# ARK.net
KiCad netlist of a schematic drawn in EAGLE
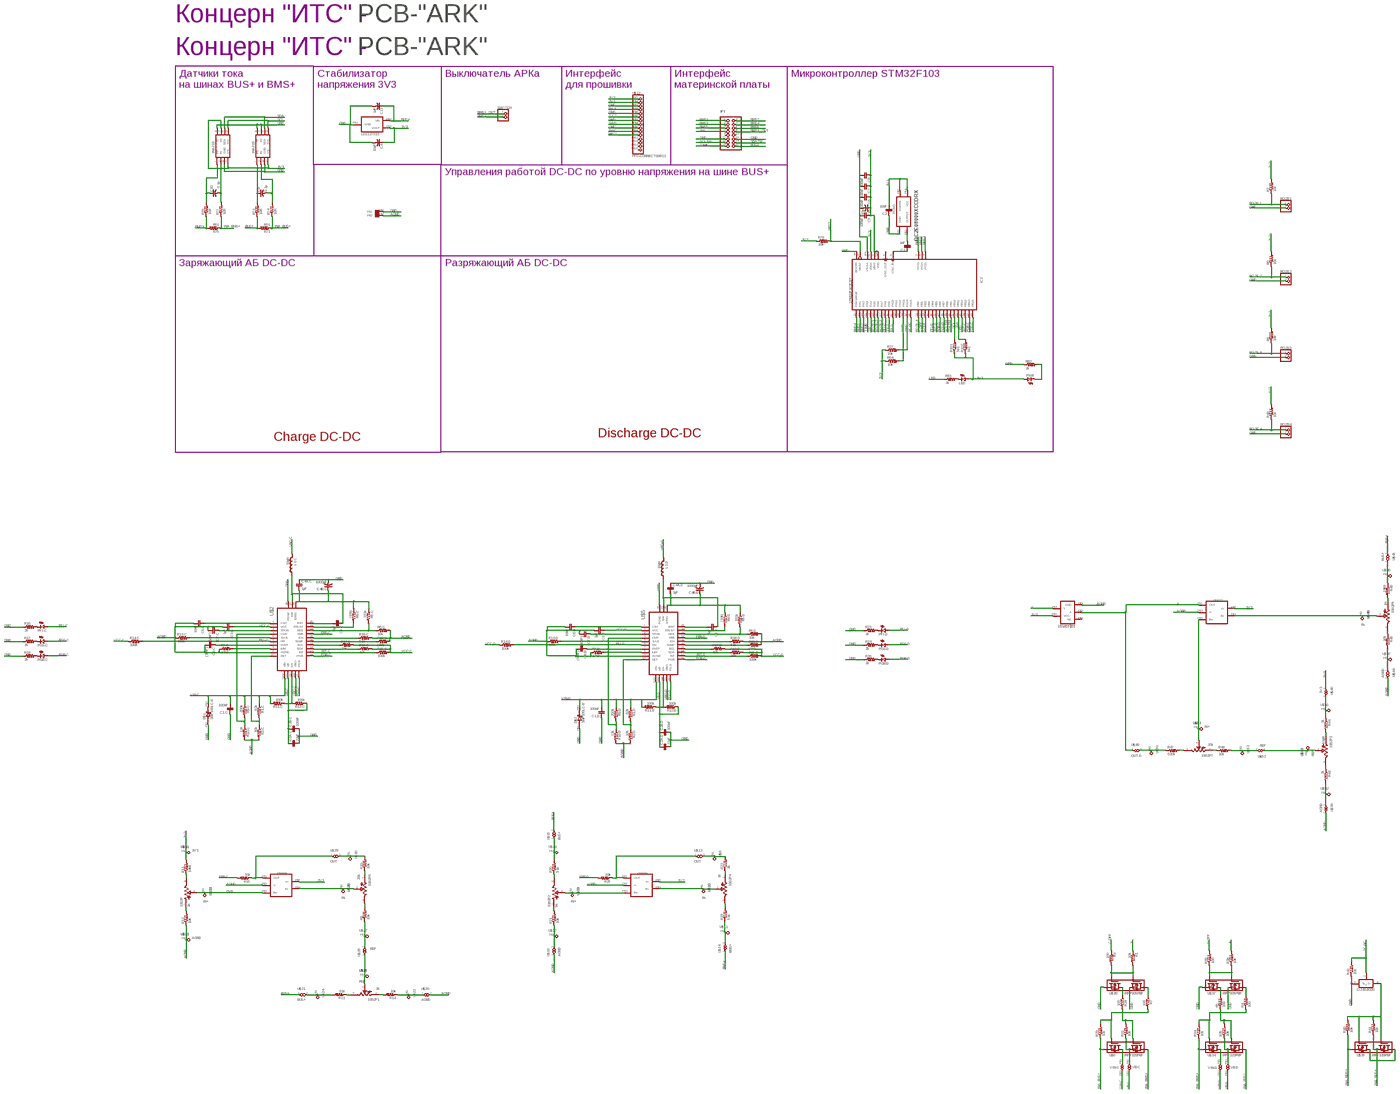
[diagram p0: schematic, sheet 1, overview]
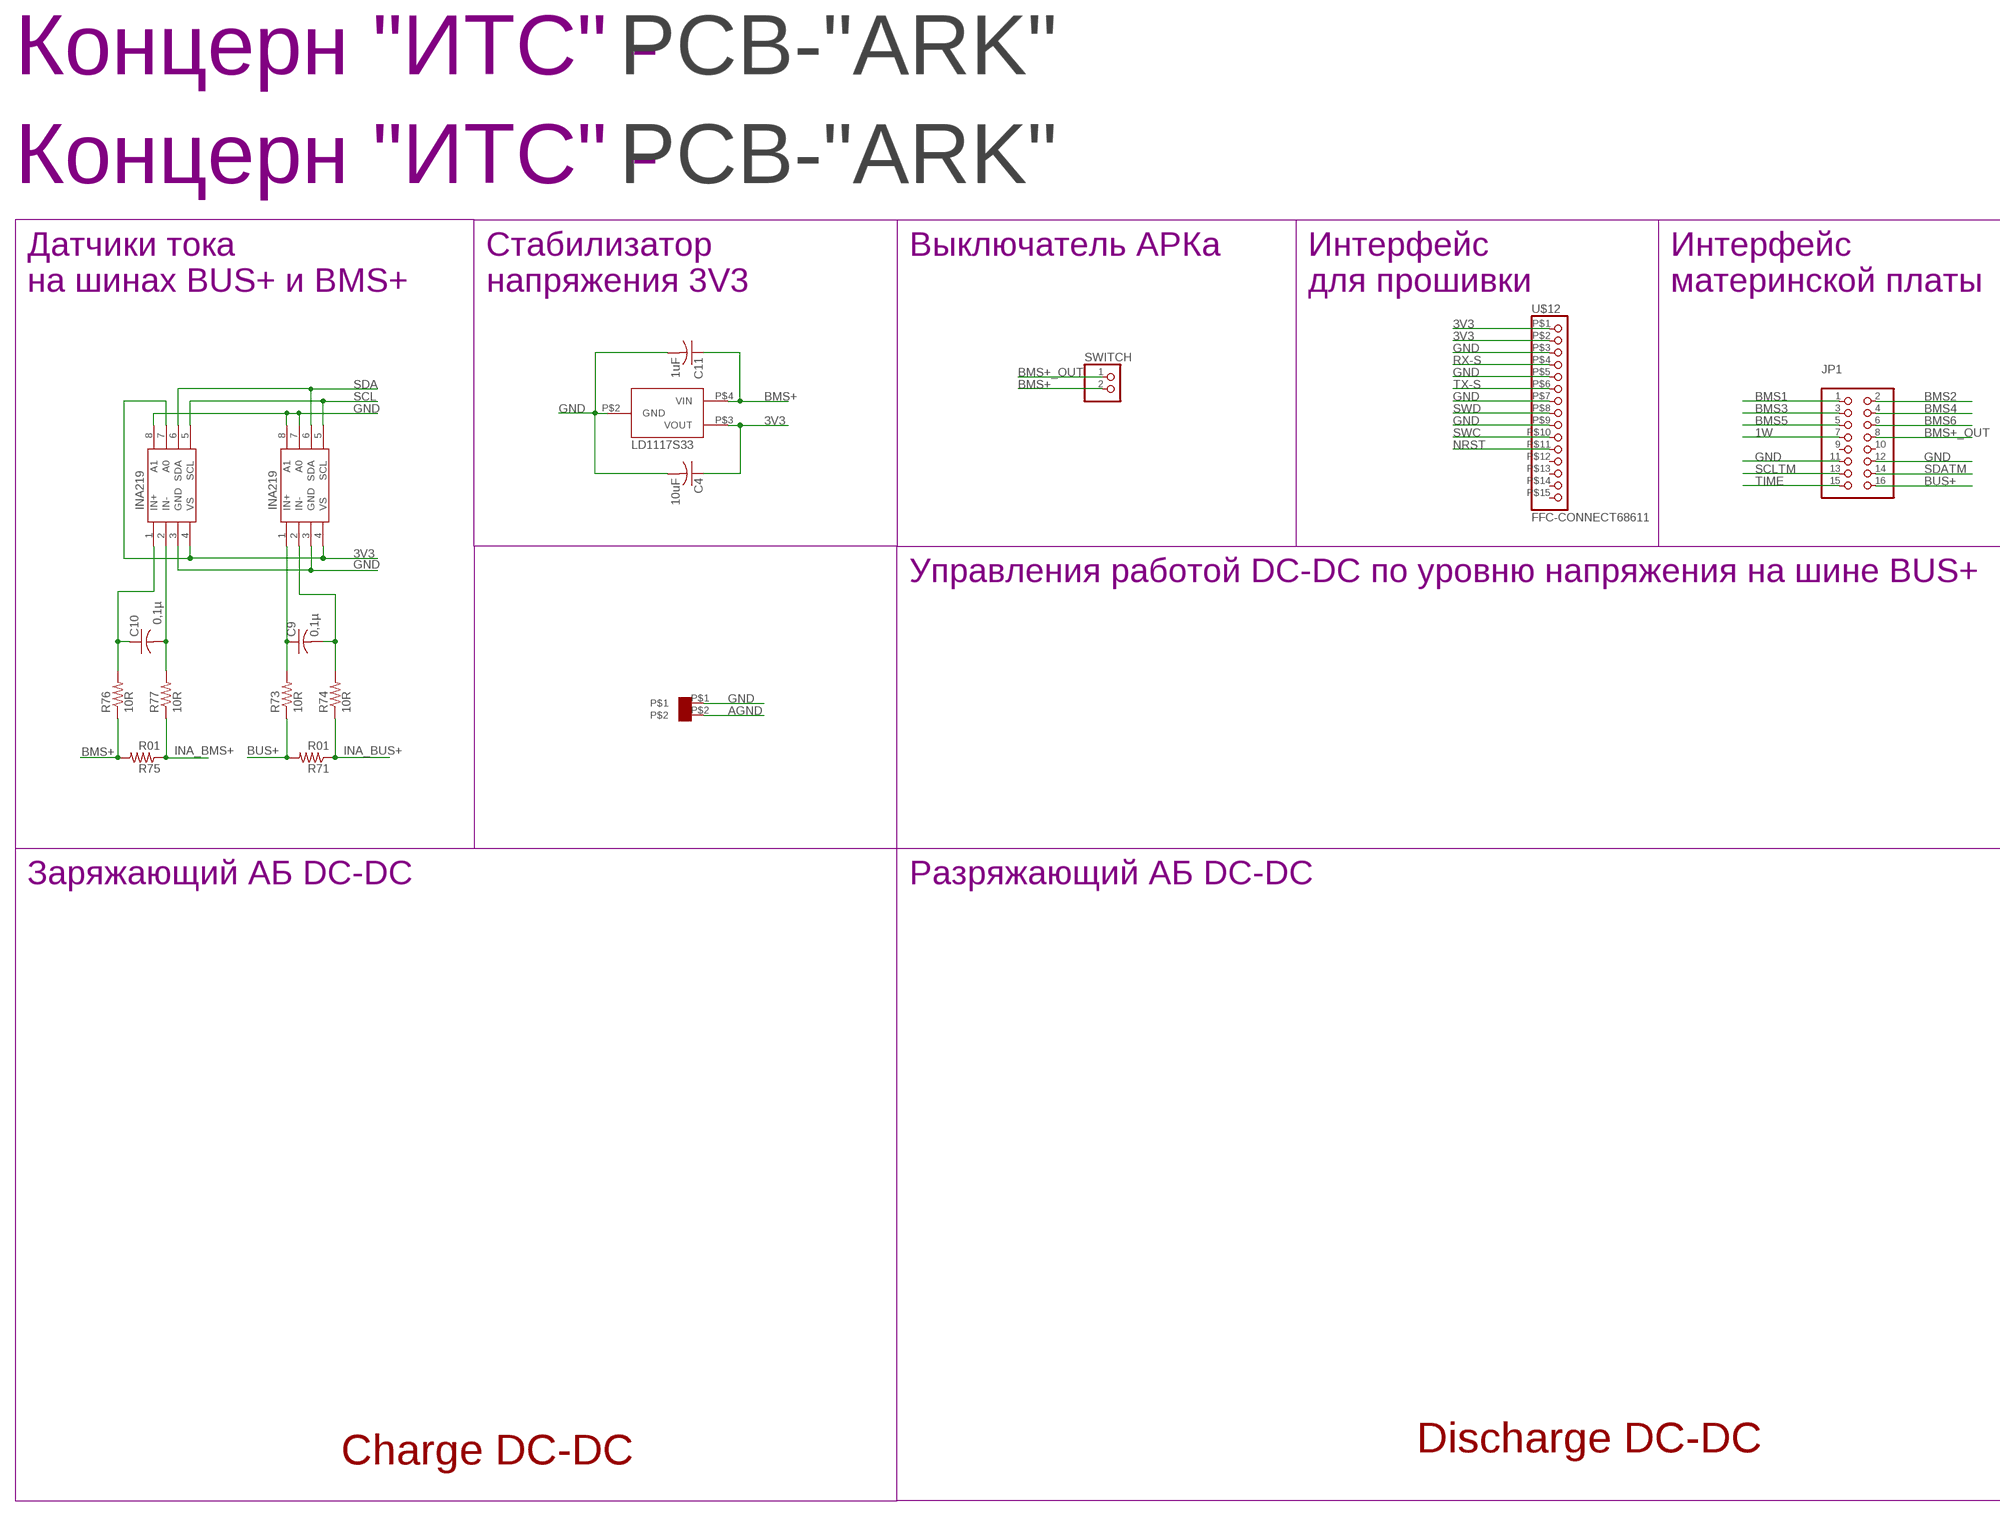
[diagram p1: schematic, sheet 1, part 1 of 4]
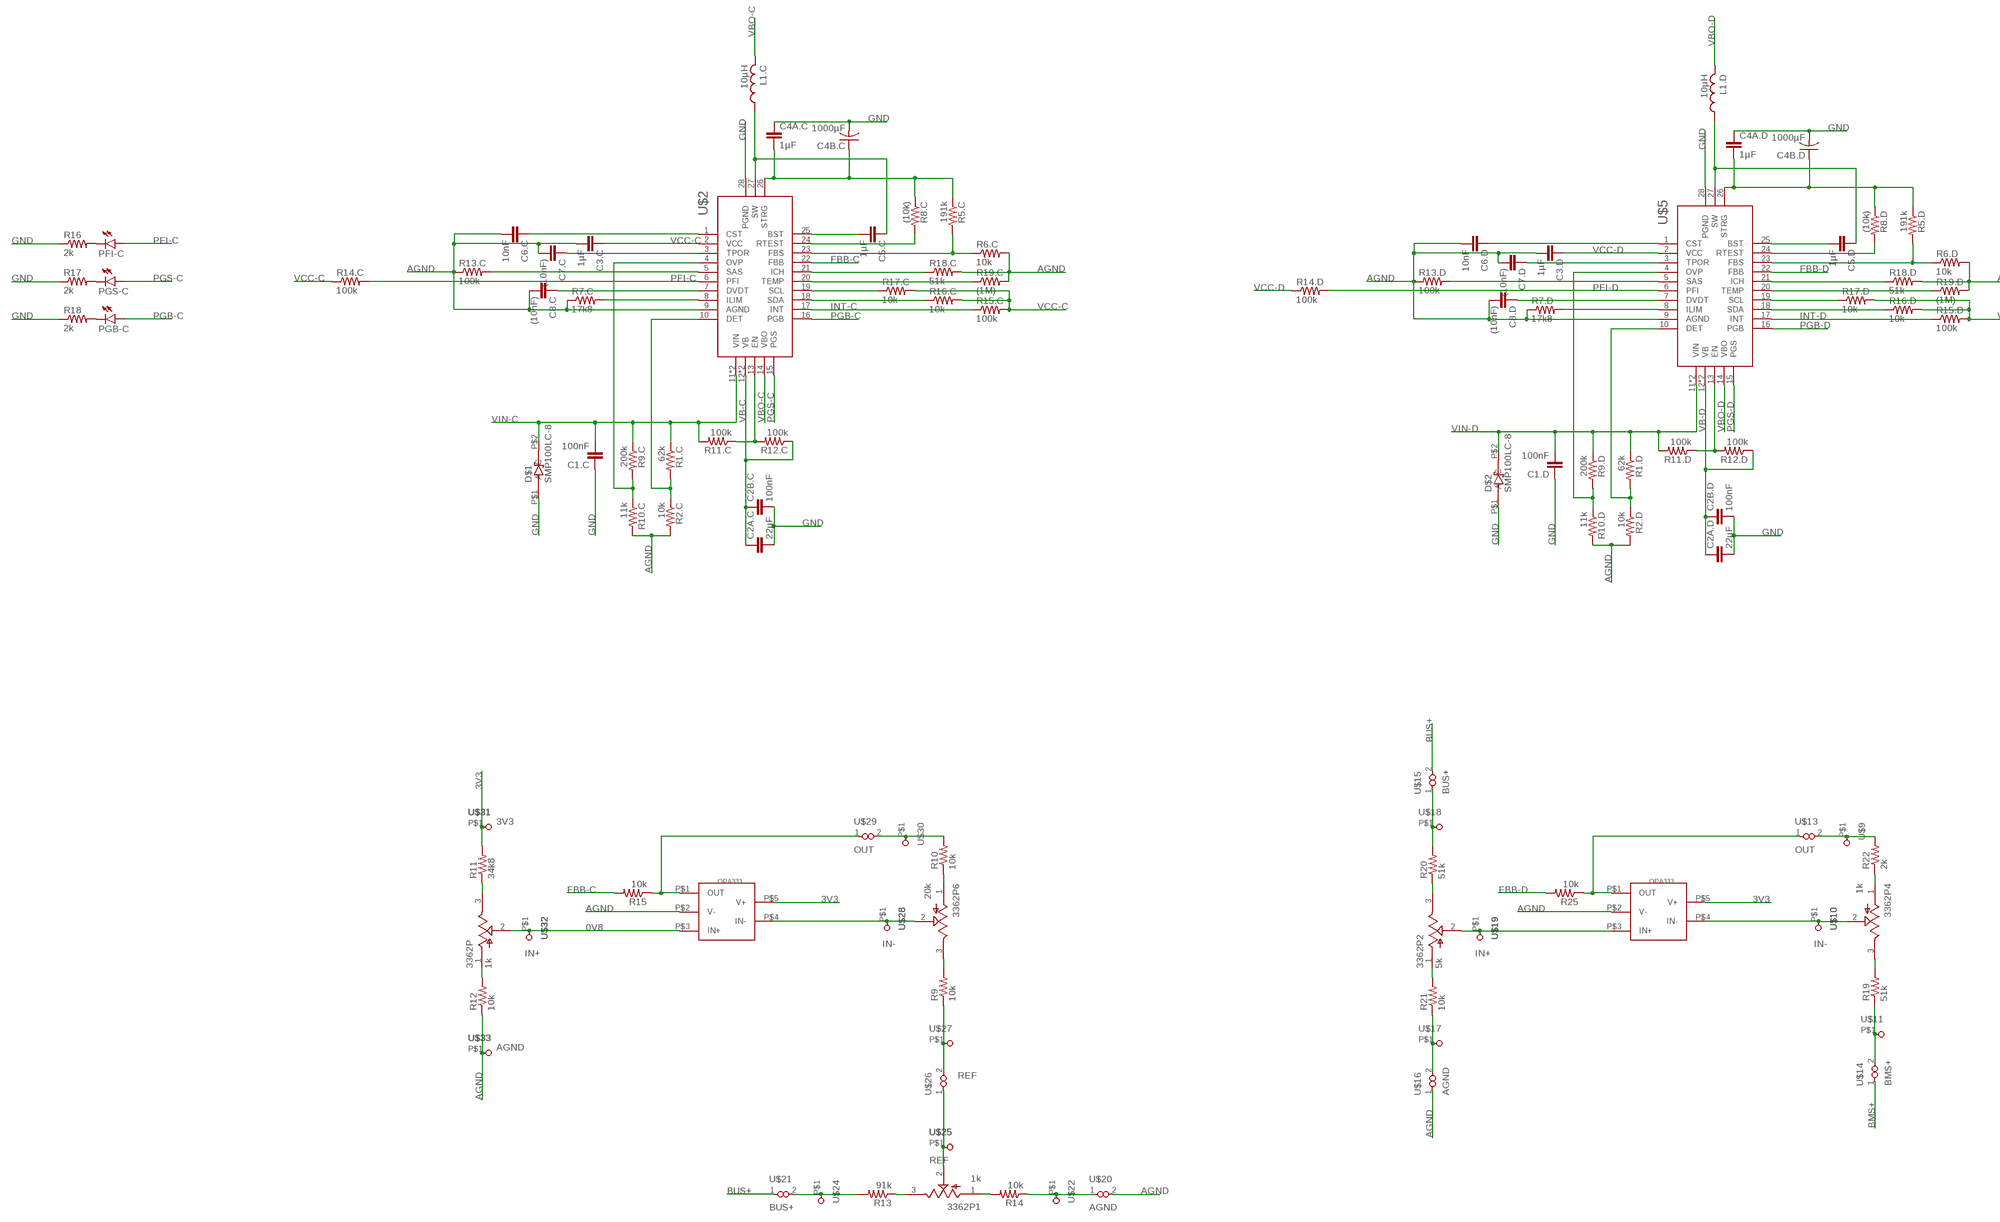
[diagram p2: schematic, sheet 1, part 2 of 4]
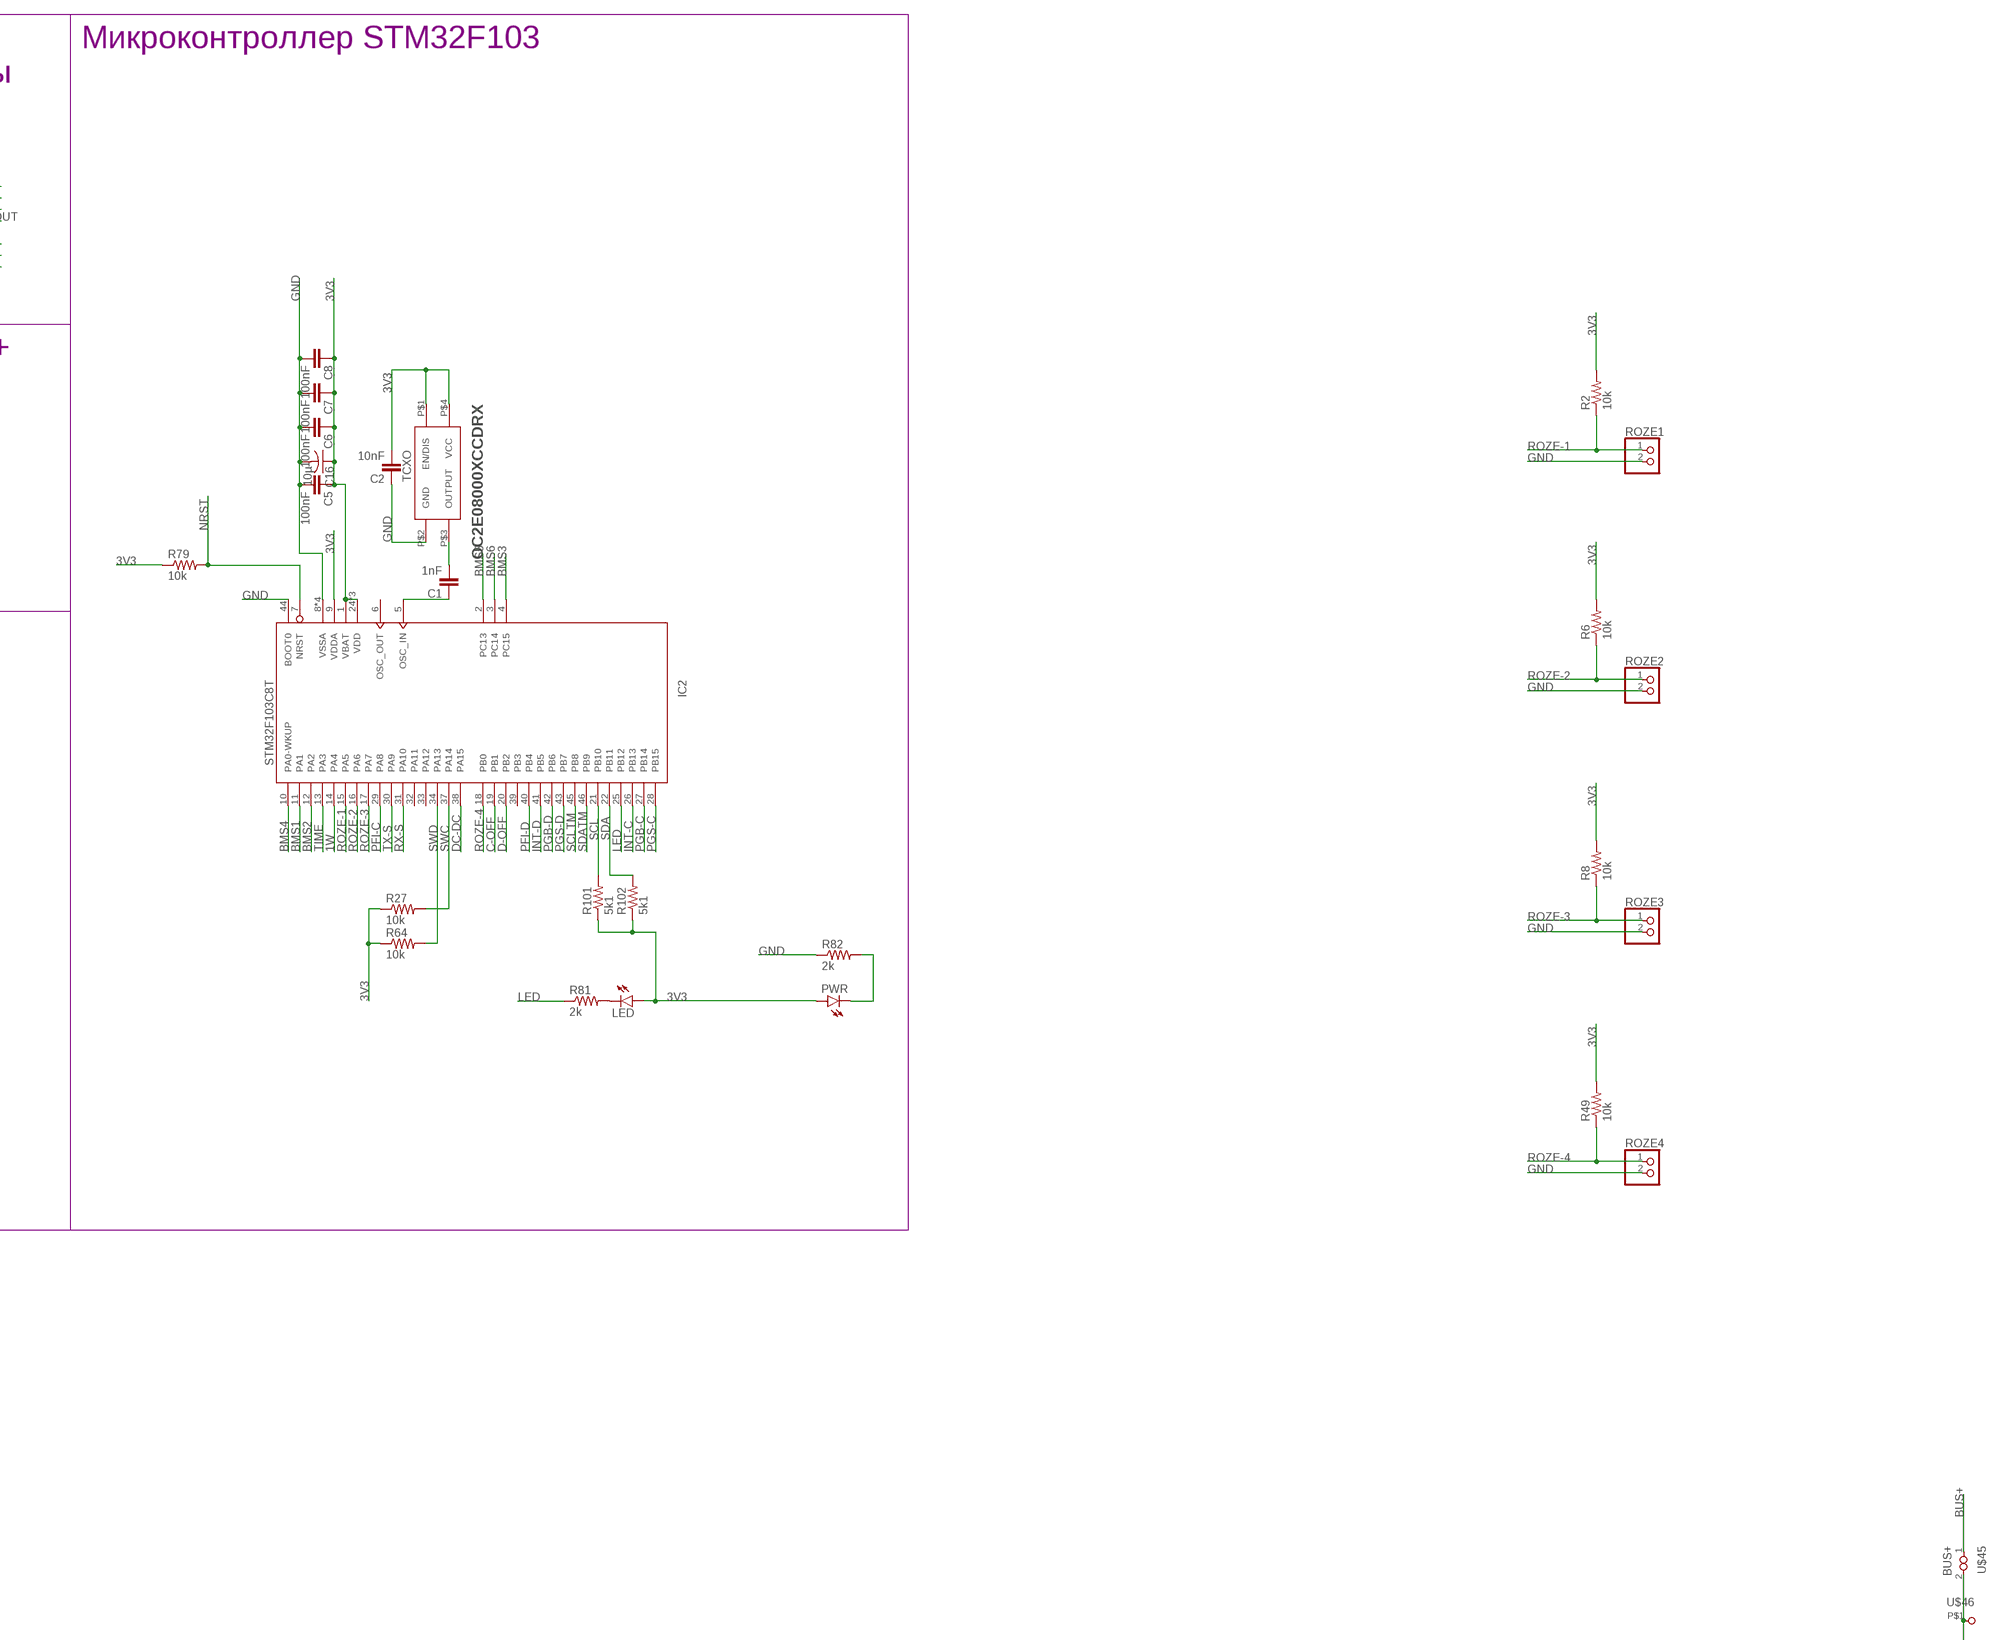
[diagram p3: schematic, sheet 1, part 3 of 4]
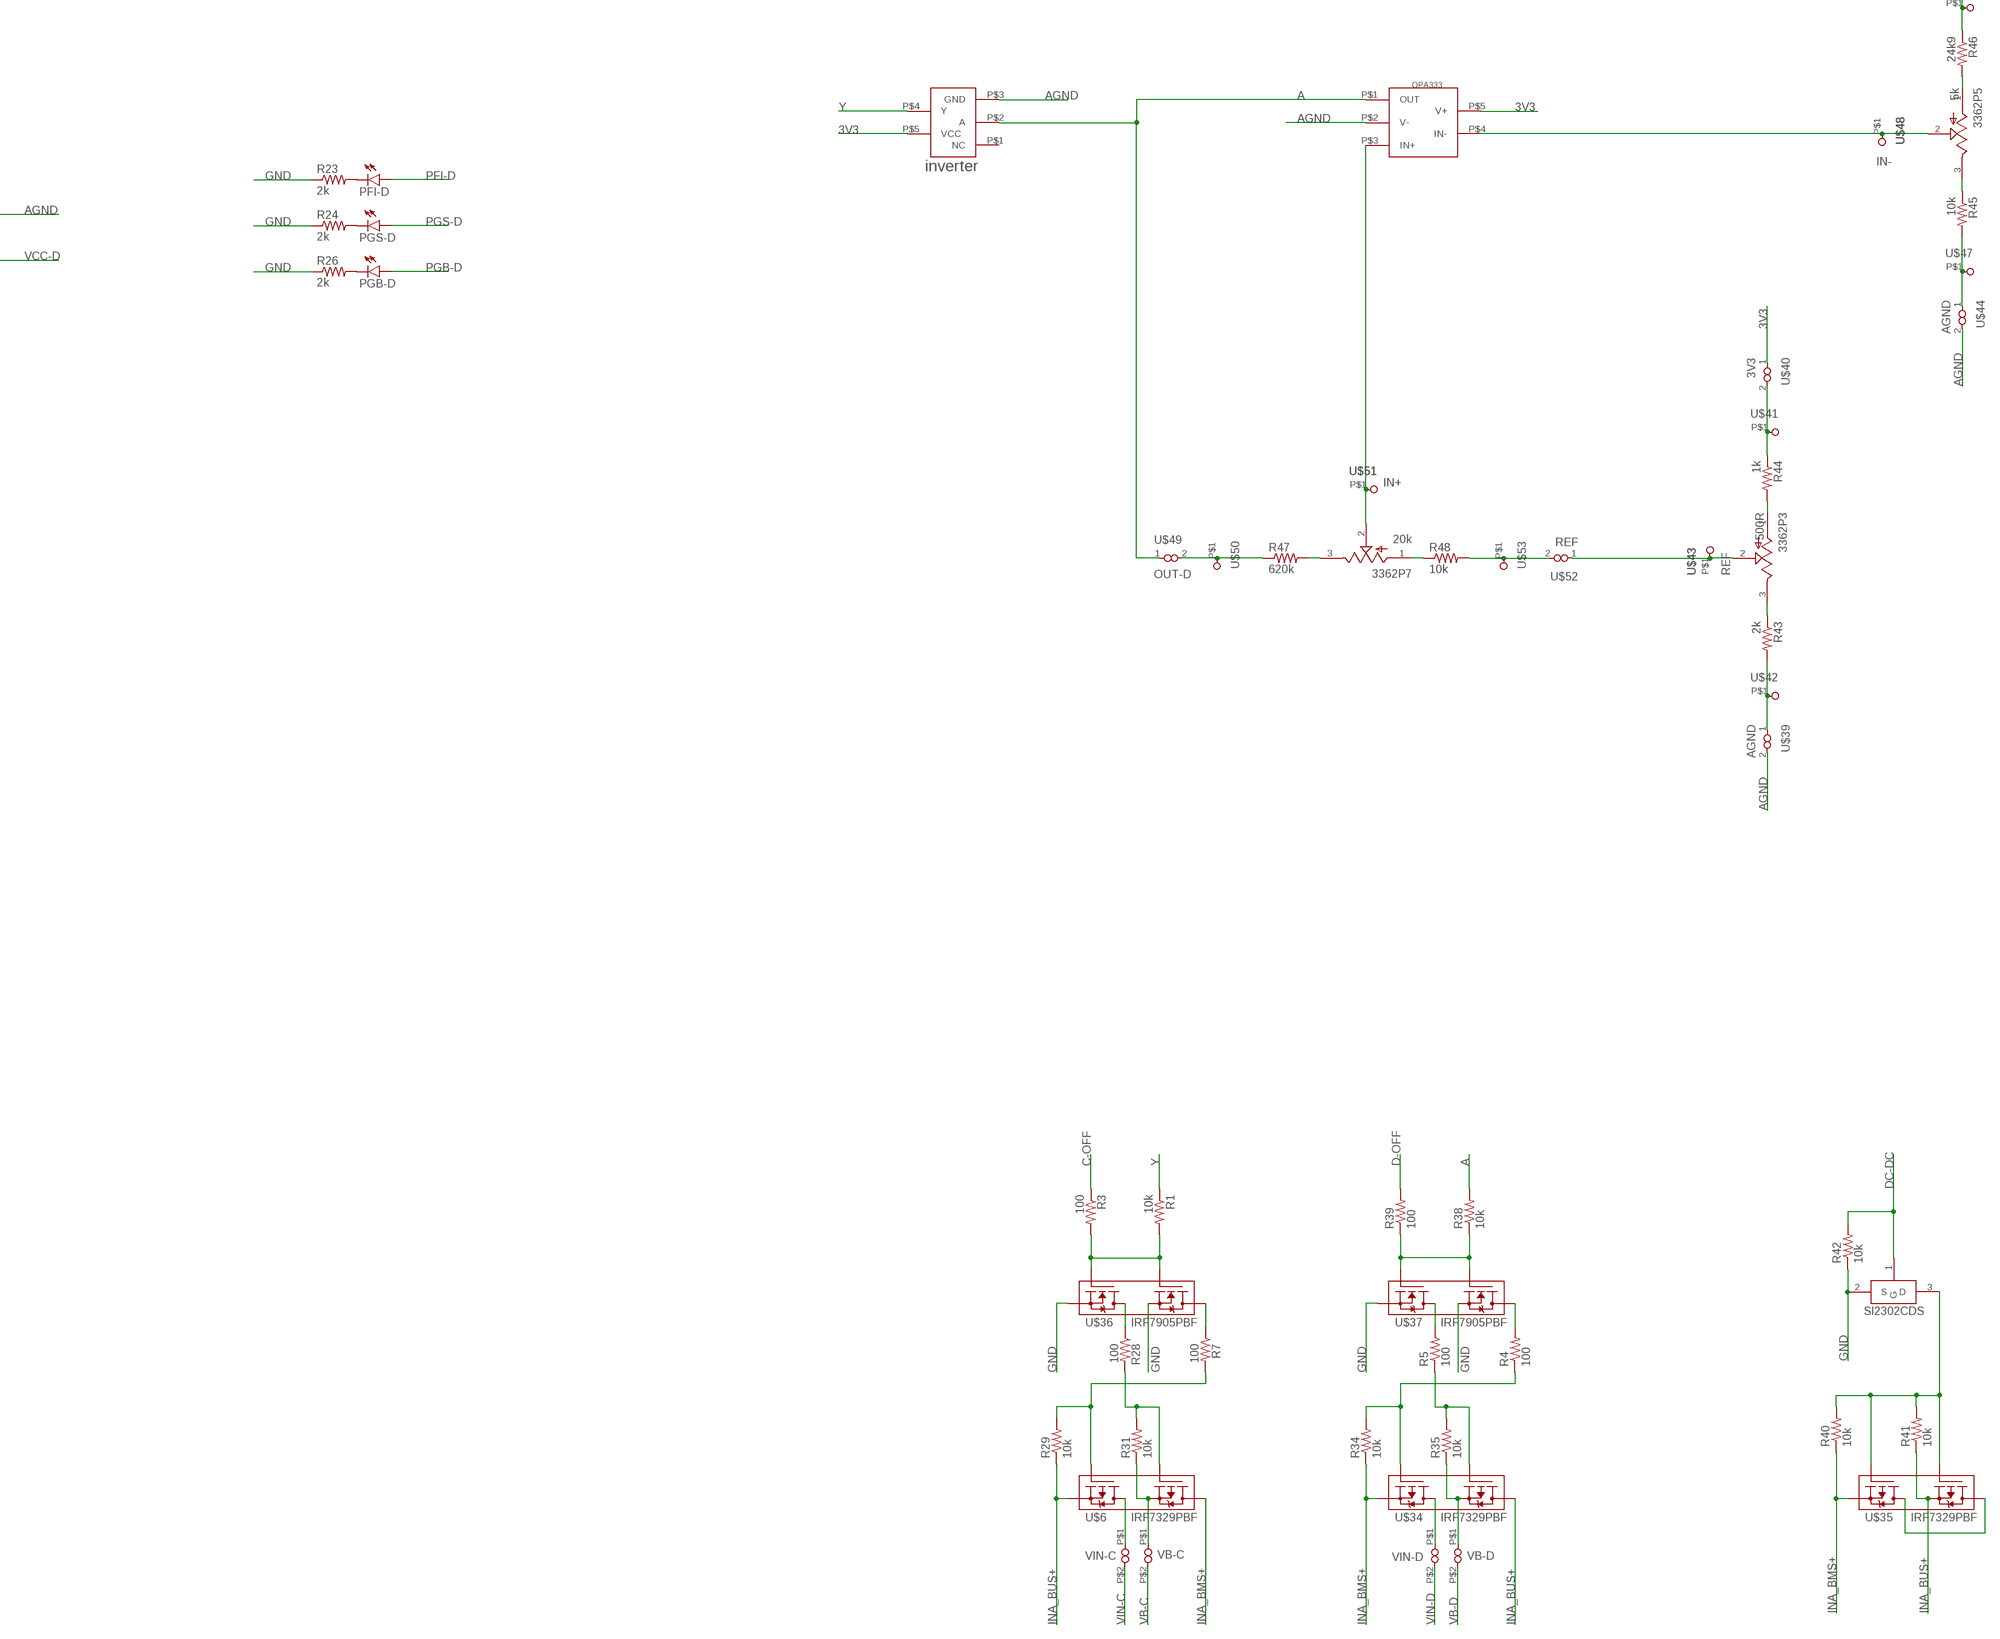
[diagram p4: schematic, sheet 1, part 4 of 4]

(export (version "E")
  (design (tool "Eeschema 10.0.6"))
  (components
    (comp (ref "3362P")
      (value "1k")
      (footprint "eagle-import:TRIM_3362P-1-502LF")
      (fields (field (name "MF") "Bourns") (field (name "MP") "3362P-1-502LF"))
      (libsource (lib "eagle-import") (part "3362P-1-502LF"))
    )
    (comp (ref "3362P1")
      (value "1k")
      (footprint "eagle-import:TRIM_3362P-1-502LF")
      (fields (field (name "MF") "Bourns") (field (name "MP") "3362P-1-502LF"))
      (libsource (lib "eagle-import") (part "3362P-1-502LF"))
    )
    (comp (ref "3362P2")
      (value "5k")
      (footprint "eagle-import:TRIM_3362P-1-502LF")
      (fields (field (name "MF") "Bourns") (field (name "MP") "3362P-1-502LF"))
      (libsource (lib "eagle-import") (part "3362P-1-502LF"))
    )
    (comp (ref "3362P3")
      (value "500R")
      (footprint "eagle-import:TRIM_3362P-1-502LF")
      (fields (field (name "MF") "Bourns") (field (name "MP") "3362P-1-502LF"))
      (libsource (lib "eagle-import") (part "3362P-1-502LF"))
    )
    (comp (ref "3362P4")
      (value "1k")
      (footprint "eagle-import:TRIM_3362P-1-502LF")
      (fields (field (name "MF") "Bourns") (field (name "MP") "3362P-1-502LF"))
      (libsource (lib "eagle-import") (part "3362P-1-502LF"))
    )
    (comp (ref "3362P5")
      (value "5k")
      (footprint "eagle-import:TRIM_3362P-1-502LF")
      (fields (field (name "MF") "Bourns") (field (name "MP") "3362P-1-502LF"))
      (libsource (lib "eagle-import") (part "3362P-1-502LF"))
    )
    (comp (ref "3362P6")
      (value "20k")
      (footprint "eagle-import:TRIM_3362P-1-502LF")
      (fields (field (name "MF") "Bourns") (field (name "MP") "3362P-1-502LF"))
      (libsource (lib "eagle-import") (part "3362P-1-502LF"))
    )
    (comp (ref "3362P7")
      (value "20k")
      (footprint "eagle-import:TRIM_3362P-1-502LF")
      (fields (field (name "MF") "Bourns") (field (name "MP") "3362P-1-502LF"))
      (libsource (lib "eagle-import") (part "3362P-1-502LF"))
    )
    (comp (ref "C1")
      (value "1nF")
      (footprint "eagle-import:C0603")
      (libsource (lib "eagle-import") (part "C-EUC0603"))
    )
    (comp (ref "C1.C")
      (value "100nF")
      (footprint "eagle-import:C0603")
      (libsource (lib "eagle-import") (part "C-EUC0603"))
    )
    (comp (ref "C1.D")
      (value "100nF")
      (footprint "eagle-import:C0603")
      (libsource (lib "eagle-import") (part "C-EUC0603"))
    )
    (comp (ref "C2")
      (value "10nF")
      (footprint "eagle-import:C0603")
      (libsource (lib "eagle-import") (part "C-EUC0603"))
    )
    (comp (ref "C2A.C")
      (value "22µF")
      (footprint "eagle-import:C1206")
      (libsource (lib "eagle-import") (part "C-EUC1206"))
    )
    (comp (ref "C2A.D")
      (value "22µF")
      (footprint "eagle-import:C1206")
      (libsource (lib "eagle-import") (part "C-EUC1206"))
    )
    (comp (ref "C2B.C")
      (value "100nF")
      (footprint "eagle-import:C0603")
      (libsource (lib "eagle-import") (part "C-EUC0603"))
    )
    (comp (ref "C2B.D")
      (value "100nF")
      (footprint "eagle-import:C0603")
      (libsource (lib "eagle-import") (part "C-EUC0603"))
    )
    (comp (ref "C3.C")
      (value "1µF")
      (footprint "eagle-import:C0603")
      (libsource (lib "eagle-import") (part "C-EUC0603"))
    )
    (comp (ref "C3.D")
      (value "1µF")
      (footprint "eagle-import:C0603")
      (libsource (lib "eagle-import") (part "C-EUC0603"))
    )
    (comp (ref "C4")
      (value "10uF")
      (footprint "eagle-import:ECAP-SMD-D4")
      (libsource (lib "eagle-import") (part "ECAP1UF"))
    )
    (comp (ref "C4A.C")
      (value "1µF")
      (footprint "eagle-import:C1206")
      (libsource (lib "eagle-import") (part "C-EUC1206"))
    )
    (comp (ref "C4A.D")
      (value "1µF")
      (footprint "eagle-import:C1206")
      (libsource (lib "eagle-import") (part "C-EUC1206"))
    )
    (comp (ref "C4B.C")
      (value "1000µF")
      (footprint "eagle-import:ECAP1000-CMD")
      (libsource (lib "eagle-import") (part "ECAPECAP1000"))
    )
    (comp (ref "C4B.D")
      (value "1000µF")
      (footprint "eagle-import:ECAP1000-CMD")
      (libsource (lib "eagle-import") (part "ECAPECAP1000"))
    )
    (comp (ref "C5")
      (value "100nF")
      (footprint "eagle-import:C0603")
      (libsource (lib "eagle-import") (part "C-EUC0603"))
    )
    (comp (ref "C5.C")
      (value "1µF")
      (footprint "eagle-import:C0603")
      (libsource (lib "eagle-import") (part "C-EUC0603"))
    )
    (comp (ref "C5.D")
      (value "1µF")
      (footprint "eagle-import:C0603")
      (libsource (lib "eagle-import") (part "C-EUC0603"))
    )
    (comp (ref "C6")
      (value "100nF")
      (footprint "eagle-import:C0603")
      (libsource (lib "eagle-import") (part "C-EUC0603"))
    )
    (comp (ref "C6.C")
      (value "10nF")
      (footprint "eagle-import:C0603")
      (libsource (lib "eagle-import") (part "C-EUC0603"))
    )
    (comp (ref "C6.D")
      (value "10nF")
      (footprint "eagle-import:C0603")
      (libsource (lib "eagle-import") (part "C-EUC0603"))
    )
    (comp (ref "C7")
      (value "100nF")
      (footprint "eagle-import:C0603")
      (libsource (lib "eagle-import") (part "C-EUC0603"))
    )
    (comp (ref "C7.C")
      (value "(10nF)")
      (footprint "eagle-import:C0603")
      (libsource (lib "eagle-import") (part "C-EUC0603"))
    )
    (comp (ref "C7.D")
      (value "(10nF)")
      (footprint "eagle-import:C0603")
      (libsource (lib "eagle-import") (part "C-EUC0603"))
    )
    (comp (ref "C8")
      (value "100nF")
      (footprint "eagle-import:C0603")
      (libsource (lib "eagle-import") (part "C-EUC0603"))
    )
    (comp (ref "C8.C")
      (value "(10nF)")
      (footprint "eagle-import:C0603")
      (libsource (lib "eagle-import") (part "C-EUC0603"))
    )
    (comp (ref "C8.D")
      (value "(10nF)")
      (footprint "eagle-import:C0603")
      (libsource (lib "eagle-import") (part "C-EUC0603"))
    )
    (comp (ref "C9")
      (value "0,1µ")
      (footprint "eagle-import:C0603")
      (libsource (lib "eagle-import") (part "C-USC0603"))
    )
    (comp (ref "C10")
      (value "0,1µ")
      (footprint "eagle-import:C0603")
      (libsource (lib "eagle-import") (part "C-USC0603"))
    )
    (comp (ref "C11")
      (value "1uF")
      (footprint "eagle-import:ECAP-SMD-D4")
      (libsource (lib "eagle-import") (part "ECAP1UF"))
    )
    (comp (ref "C16")
      (value "10µ")
      (footprint "eagle-import:C1206")
      (libsource (lib "eagle-import") (part "C-USC1206"))
    )
    (comp (ref "D$1")
      (value "SMP100LC-8")
      (footprint "eagle-import:SMB")
      (libsource (lib "eagle-import") (part "SMP100LC-8"))
    )
    (comp (ref "D$2")
      (value "SMP100LC-8")
      (footprint "eagle-import:SMB")
      (libsource (lib "eagle-import") (part "SMP100LC-8"))
    )
    (comp (ref "IC2")
      (value "STM32F103C8T")
      (footprint "eagle-import:LQFP48")
      (libsource (lib "eagle-import") (part "STM32F103CT8"))
    )
    (comp (ref "INA219#1")
      (value "INA219AID")
      (footprint "eagle-import:SOT23-8")
      (libsource (lib "eagle-import") (part "INA219AID"))
    )
    (comp (ref "INA219#2")
      (value "INA219AID")
      (footprint "eagle-import:SOT23-8")
      (libsource (lib "eagle-import") (part "INA219AID"))
    )
    (comp (ref "INVERT1")
      (value "INVERTER.")
      (footprint "eagle-import:SC70")
      (libsource (lib "eagle-import") (part "INVERTER."))
    )
    (comp (ref "JP1")
      (value "PINHD-2X8")
      (footprint "eagle-import:2X08")
      (libsource (lib "eagle-import") (part "PINHD-2X8"))
    )
    (comp (ref "L1.C")
      (value "10µH")
      (footprint "eagle-import:L_12X12")
      (libsource (lib "eagle-import") (part "L_10MKH"))
    )
    (comp (ref "L1.D")
      (value "10µH")
      (footprint "eagle-import:L_12X12")
      (libsource (lib "eagle-import") (part "L_10MKH"))
    )
    (comp (ref "LD1117S33")
      (value "LD1117S33")
      (footprint "eagle-import:SOT223")
      (libsource (lib "eagle-import") (part "LD1117S33"))
    )
    (comp (ref "LED")
      (value "LEDCHIPLED_0603")
      (footprint "eagle-import:CHIPLED_0603")
      (libsource (lib "eagle-import") (part "LEDCHIPLED_0603"))
    )
    (comp (ref "OPA1")
      (value "OPA333")
      (footprint "eagle-import:SOT23-5")
      (libsource (lib "eagle-import") (part "OPA333"))
    )
    (comp (ref "OPA2")
      (value "OPA333")
      (footprint "eagle-import:SOT23-5")
      (libsource (lib "eagle-import") (part "OPA333"))
    )
    (comp (ref "OPA3")
      (value "OPA333")
      (footprint "eagle-import:SOT23-5")
      (libsource (lib "eagle-import") (part "OPA333"))
    )
    (comp (ref "PFI-C")
      (value "LEDCHIPLED_0603")
      (footprint "eagle-import:CHIPLED_0603")
      (libsource (lib "eagle-import") (part "LEDCHIPLED_0603"))
    )
    (comp (ref "PFI-D")
      (value "LEDCHIPLED_0603")
      (footprint "eagle-import:CHIPLED_0603")
      (libsource (lib "eagle-import") (part "LEDCHIPLED_0603"))
    )
    (comp (ref "PGB-C")
      (value "LEDCHIPLED_0603")
      (footprint "eagle-import:CHIPLED_0603")
      (libsource (lib "eagle-import") (part "LEDCHIPLED_0603"))
    )
    (comp (ref "PGB-D")
      (value "LEDCHIPLED_0603")
      (footprint "eagle-import:CHIPLED_0603")
      (libsource (lib "eagle-import") (part "LEDCHIPLED_0603"))
    )
    (comp (ref "PGS-C")
      (value "LEDCHIPLED_0603")
      (footprint "eagle-import:CHIPLED_0603")
      (libsource (lib "eagle-import") (part "LEDCHIPLED_0603"))
    )
    (comp (ref "PGS-D")
      (value "LEDCHIPLED_0603")
      (footprint "eagle-import:CHIPLED_0603")
      (libsource (lib "eagle-import") (part "LEDCHIPLED_0603"))
    )
    (comp (ref "PWR")
      (value "LEDCHIPLED_0603")
      (footprint "eagle-import:CHIPLED_0603")
      (libsource (lib "eagle-import") (part "LEDCHIPLED_0603"))
    )
    (comp (ref "R1")
      (value "10k")
      (footprint "eagle-import:R0603")
      (libsource (lib "eagle-import") (part "resistor_348_R-US_R0603"))
    )
    (comp (ref "R1.C")
      (value "62k")
      (footprint "eagle-import:R0603")
      (libsource (lib "eagle-import") (part "R-US_R0603"))
    )
    (comp (ref "R1.D")
      (value "62k")
      (footprint "eagle-import:R0603")
      (libsource (lib "eagle-import") (part "R-US_R0603"))
    )
    (comp (ref "R2")
      (value "10k")
      (footprint "eagle-import:R0603")
      (libsource (lib "eagle-import") (part "resistor_348_R-US_R0603"))
    )
    (comp (ref "R2.C")
      (value "10k")
      (footprint "eagle-import:R0603")
      (libsource (lib "eagle-import") (part "R-US_R0603"))
    )
    (comp (ref "R2.D")
      (value "10k")
      (footprint "eagle-import:R0603")
      (libsource (lib "eagle-import") (part "R-US_R0603"))
    )
    (comp (ref "R3")
      (value "100")
      (footprint "eagle-import:R0603")
      (libsource (lib "eagle-import") (part "resistor_348_R-US_R0603"))
    )
    (comp (ref "R4")
      (value "100")
      (footprint "eagle-import:R0603")
      (libsource (lib "eagle-import") (part "resistor_348_R-US_R0603"))
    )
    (comp (ref "R5")
      (value "100")
      (footprint "eagle-import:R0603")
      (libsource (lib "eagle-import") (part "resistor_348_R-US_R0603"))
    )
    (comp (ref "R5.C")
      (value "191k")
      (footprint "eagle-import:R0603")
      (libsource (lib "eagle-import") (part "R-US_R0603"))
    )
    (comp (ref "R5.D")
      (value "191k")
      (footprint "eagle-import:R0603")
      (libsource (lib "eagle-import") (part "R-US_R0603"))
    )
    (comp (ref "R6")
      (value "10k")
      (footprint "eagle-import:R0603")
      (libsource (lib "eagle-import") (part "resistor_348_R-US_R0603"))
    )
    (comp (ref "R6.C")
      (value "10k")
      (footprint "eagle-import:R0603")
      (libsource (lib "eagle-import") (part "R-US_R0603"))
    )
    (comp (ref "R6.D")
      (value "10k")
      (footprint "eagle-import:R0603")
      (libsource (lib "eagle-import") (part "R-US_R0603"))
    )
    (comp (ref "R7")
      (value "100")
      (footprint "eagle-import:R0603")
      (libsource (lib "eagle-import") (part "resistor_348_R-US_R0603"))
    )
    (comp (ref "R7.C")
      (value "17k8")
      (footprint "eagle-import:R0603")
      (libsource (lib "eagle-import") (part "R-US_R0603"))
    )
    (comp (ref "R7.D")
      (value "17k8")
      (footprint "eagle-import:R0603")
      (libsource (lib "eagle-import") (part "R-US_R0603"))
    )
    (comp (ref "R8")
      (value "10k")
      (footprint "eagle-import:R0603")
      (libsource (lib "eagle-import") (part "resistor_348_R-US_R0603"))
    )
    (comp (ref "R8.C")
      (value "(10k)")
      (footprint "eagle-import:R0603")
      (libsource (lib "eagle-import") (part "R-US_R0603"))
    )
    (comp (ref "R8.D")
      (value "(10k)")
      (footprint "eagle-import:R0603")
      (libsource (lib "eagle-import") (part "R-US_R0603"))
    )
    (comp (ref "R9")
      (value "10k")
      (footprint "eagle-import:R0603")
      (libsource (lib "eagle-import") (part "resistor_348_R-US_R0603"))
    )
    (comp (ref "R9.C")
      (value "200k")
      (footprint "eagle-import:R0603")
      (libsource (lib "eagle-import") (part "R-US_R0603"))
    )
    (comp (ref "R9.D")
      (value "200k")
      (footprint "eagle-import:R0603")
      (libsource (lib "eagle-import") (part "R-US_R0603"))
    )
    (comp (ref "R10")
      (value "10k")
      (footprint "eagle-import:R0603")
      (libsource (lib "eagle-import") (part "resistor_348_R-US_R0603"))
    )
    (comp (ref "R10.C")
      (value "11k")
      (footprint "eagle-import:R0603")
      (libsource (lib "eagle-import") (part "R-US_R0603"))
    )
    (comp (ref "R10.D")
      (value "11k")
      (footprint "eagle-import:R0603")
      (libsource (lib "eagle-import") (part "R-US_R0603"))
    )
    (comp (ref "R11")
      (value "34k8")
      (footprint "eagle-import:R0603")
      (libsource (lib "eagle-import") (part "resistor_348_R-US_R0603"))
    )
    (comp (ref "R11.C")
      (value "100k")
      (footprint "eagle-import:R0603")
      (libsource (lib "eagle-import") (part "R-US_R0603"))
    )
    (comp (ref "R11.D")
      (value "100k")
      (footprint "eagle-import:R0603")
      (libsource (lib "eagle-import") (part "R-US_R0603"))
    )
    (comp (ref "R12")
      (value "10k")
      (footprint "eagle-import:R0603")
      (libsource (lib "eagle-import") (part "resistor_348_R-US_R0603"))
    )
    (comp (ref "R12.C")
      (value "100k")
      (footprint "eagle-import:R0603")
      (libsource (lib "eagle-import") (part "R-US_R0603"))
    )
    (comp (ref "R12.D")
      (value "100k")
      (footprint "eagle-import:R0603")
      (libsource (lib "eagle-import") (part "R-US_R0603"))
    )
    (comp (ref "R13")
      (value "91k")
      (footprint "eagle-import:R0603")
      (libsource (lib "eagle-import") (part "resistor_348_R-US_R0603"))
    )
    (comp (ref "R13.C")
      (value "100k")
      (footprint "eagle-import:R0603")
      (libsource (lib "eagle-import") (part "R-US_R0603"))
    )
    (comp (ref "R13.D")
      (value "100k")
      (footprint "eagle-import:R0603")
      (libsource (lib "eagle-import") (part "R-US_R0603"))
    )
    (comp (ref "R14")
      (value "10k")
      (footprint "eagle-import:R0603")
      (libsource (lib "eagle-import") (part "resistor_348_R-US_R0603"))
    )
    (comp (ref "R14.C")
      (value "100k")
      (footprint "eagle-import:R0603")
      (libsource (lib "eagle-import") (part "R-US_R0603"))
    )
    (comp (ref "R14.D")
      (value "100k")
      (footprint "eagle-import:R0603")
      (libsource (lib "eagle-import") (part "R-US_R0603"))
    )
    (comp (ref "R15")
      (value "10k")
      (footprint "eagle-import:R0603")
      (libsource (lib "eagle-import") (part "resistor_348_R-US_R0603"))
    )
    (comp (ref "R15.C")
      (value "100k")
      (footprint "eagle-import:R0603")
      (libsource (lib "eagle-import") (part "R-US_R0603"))
    )
    (comp (ref "R15.D")
      (value "100k")
      (footprint "eagle-import:R0603")
      (libsource (lib "eagle-import") (part "R-US_R0603"))
    )
    (comp (ref "R16")
      (value "2k")
      (footprint "eagle-import:R0603")
      (libsource (lib "eagle-import") (part "resistor_348_R-US_R0603"))
    )
    (comp (ref "R16.C")
      (value "10k")
      (footprint "eagle-import:R0603")
      (libsource (lib "eagle-import") (part "R-US_R0603"))
    )
    (comp (ref "R16.D")
      (value "10k")
      (footprint "eagle-import:R0603")
      (libsource (lib "eagle-import") (part "R-US_R0603"))
    )
    (comp (ref "R17")
      (value "2k")
      (footprint "eagle-import:R0603")
      (libsource (lib "eagle-import") (part "resistor_348_R-US_R0603"))
    )
    (comp (ref "R17.C")
      (value "10k")
      (footprint "eagle-import:R0603")
      (libsource (lib "eagle-import") (part "R-US_R0603"))
    )
    (comp (ref "R17.D")
      (value "10k")
      (footprint "eagle-import:R0603")
      (libsource (lib "eagle-import") (part "R-US_R0603"))
    )
    (comp (ref "R18")
      (value "2k")
      (footprint "eagle-import:R0603")
      (libsource (lib "eagle-import") (part "resistor_348_R-US_R0603"))
    )
    (comp (ref "R18.C")
      (value "51k")
      (footprint "eagle-import:R0603")
      (libsource (lib "eagle-import") (part "R-US_R0603"))
    )
    (comp (ref "R18.D")
      (value "51k")
      (footprint "eagle-import:R0603")
      (libsource (lib "eagle-import") (part "R-US_R0603"))
    )
    (comp (ref "R19")
      (value "51k")
      (footprint "eagle-import:R0603")
      (libsource (lib "eagle-import") (part "resistor_348_R-US_R0603"))
    )
    (comp (ref "R19.C")
      (value "(1M)")
      (footprint "eagle-import:R0603")
      (libsource (lib "eagle-import") (part "R-US_R0603"))
    )
    (comp (ref "R19.D")
      (value "(1M)")
      (footprint "eagle-import:R0603")
      (libsource (lib "eagle-import") (part "R-US_R0603"))
    )
    (comp (ref "R20")
      (value "51k")
      (footprint "eagle-import:R0603")
      (libsource (lib "eagle-import") (part "resistor_348_R-US_R0603"))
    )
    (comp (ref "R21")
      (value "10k")
      (footprint "eagle-import:R0603")
      (libsource (lib "eagle-import") (part "resistor_348_R-US_R0603"))
    )
    (comp (ref "R22")
      (value "2k")
      (footprint "eagle-import:R0603")
      (libsource (lib "eagle-import") (part "resistor_348_R-US_R0603"))
    )
    (comp (ref "R23")
      (value "2k")
      (footprint "eagle-import:R0603")
      (libsource (lib "eagle-import") (part "resistor_348_R-US_R0603"))
    )
    (comp (ref "R24")
      (value "2k")
      (footprint "eagle-import:R0603")
      (libsource (lib "eagle-import") (part "resistor_348_R-US_R0603"))
    )
    (comp (ref "R25")
      (value "10k")
      (footprint "eagle-import:R0603")
      (libsource (lib "eagle-import") (part "resistor_348_R-US_R0603"))
    )
    (comp (ref "R26")
      (value "2k")
      (footprint "eagle-import:R0603")
      (libsource (lib "eagle-import") (part "resistor_348_R-US_R0603"))
    )
    (comp (ref "R27")
      (value "10k")
      (footprint "eagle-import:R0603")
      (libsource (lib "eagle-import") (part "resistor_348_R-US_R0603"))
    )
    (comp (ref "R28")
      (value "100")
      (footprint "eagle-import:R0603")
      (libsource (lib "eagle-import") (part "resistor_348_R-US_R0603"))
    )
    (comp (ref "R29")
      (value "10k")
      (footprint "eagle-import:R0603")
      (libsource (lib "eagle-import") (part "resistor_348_R-US_R0603"))
    )
    (comp (ref "R31")
      (value "10k")
      (footprint "eagle-import:R0603")
      (libsource (lib "eagle-import") (part "resistor_348_R-US_R0603"))
    )
    (comp (ref "R34")
      (value "10k")
      (footprint "eagle-import:R0603")
      (libsource (lib "eagle-import") (part "resistor_348_R-US_R0603"))
    )
    (comp (ref "R35")
      (value "10k")
      (footprint "eagle-import:R0603")
      (libsource (lib "eagle-import") (part "resistor_348_R-US_R0603"))
    )
    (comp (ref "R38")
      (value "10k")
      (footprint "eagle-import:R0603")
      (libsource (lib "eagle-import") (part "resistor_348_R-US_R0603"))
    )
    (comp (ref "R39")
      (value "100")
      (footprint "eagle-import:R0603")
      (libsource (lib "eagle-import") (part "resistor_348_R-US_R0603"))
    )
    (comp (ref "R40")
      (value "10k")
      (footprint "eagle-import:R0603")
      (libsource (lib "eagle-import") (part "resistor_348_R-US_R0603"))
    )
    (comp (ref "R41")
      (value "10k")
      (footprint "eagle-import:R0603")
      (libsource (lib "eagle-import") (part "resistor_348_R-US_R0603"))
    )
    (comp (ref "R42")
      (value "10k")
      (footprint "eagle-import:R0603")
      (libsource (lib "eagle-import") (part "resistor_348_R-US_R0603"))
    )
    (comp (ref "R43")
      (value "2k")
      (footprint "eagle-import:R0603")
      (libsource (lib "eagle-import") (part "resistor_348_R-US_R0603"))
    )
    (comp (ref "R44")
      (value "1k")
      (footprint "eagle-import:R0603")
      (libsource (lib "eagle-import") (part "resistor_348_R-US_R0603"))
    )
    (comp (ref "R45")
      (value "10k")
      (footprint "eagle-import:R0603")
      (libsource (lib "eagle-import") (part "resistor_348_R-US_R0603"))
    )
    (comp (ref "R46")
      (value "24k9")
      (footprint "eagle-import:R0603")
      (libsource (lib "eagle-import") (part "resistor_348_R-US_R0603"))
    )
    (comp (ref "R47")
      (value "620k")
      (footprint "eagle-import:R0603")
      (libsource (lib "eagle-import") (part "resistor_348_R-US_R0603"))
    )
    (comp (ref "R48")
      (value "10k")
      (footprint "eagle-import:R0603")
      (libsource (lib "eagle-import") (part "resistor_348_R-US_R0603"))
    )
    (comp (ref "R49")
      (value "10k")
      (footprint "eagle-import:R0603")
      (libsource (lib "eagle-import") (part "resistor_348_R-US_R0603"))
    )
    (comp (ref "R64")
      (value "10k")
      (footprint "eagle-import:R0603")
      (libsource (lib "eagle-import") (part "resistor_348_R-US_R0603"))
    )
    (comp (ref "R71")
      (value "R01")
      (footprint "eagle-import:R2512")
      (libsource (lib "eagle-import") (part "R-US_R2512"))
    )
    (comp (ref "R73")
      (value "10R")
      (footprint "eagle-import:R0603")
      (libsource (lib "eagle-import") (part "resistor_348_R-US_R0603"))
    )
    (comp (ref "R74")
      (value "10R")
      (footprint "eagle-import:R0603")
      (libsource (lib "eagle-import") (part "resistor_348_R-US_R0603"))
    )
    (comp (ref "R75")
      (value "R01")
      (footprint "eagle-import:R2512")
      (libsource (lib "eagle-import") (part "R-US_R2512"))
    )
    (comp (ref "R76")
      (value "10R")
      (footprint "eagle-import:R0603")
      (libsource (lib "eagle-import") (part "resistor_348_R-US_R0603"))
    )
    (comp (ref "R77")
      (value "10R")
      (footprint "eagle-import:R0603")
      (libsource (lib "eagle-import") (part "resistor_348_R-US_R0603"))
    )
    (comp (ref "R79")
      (value "10k")
      (footprint "eagle-import:R0603")
      (libsource (lib "eagle-import") (part "resistor_348_R-US_R0603"))
    )
    (comp (ref "R81")
      (value "2k")
      (footprint "eagle-import:R0603")
      (libsource (lib "eagle-import") (part "resistor_348_R-US_R0603"))
    )
    (comp (ref "R82")
      (value "2k")
      (footprint "eagle-import:R0603")
      (libsource (lib "eagle-import") (part "resistor_348_R-US_R0603"))
    )
    (comp (ref "R101")
      (value "5k1")
      (footprint "eagle-import:R0603")
      (libsource (lib "eagle-import") (part "resistor_348_R-US_R0603"))
    )
    (comp (ref "R102")
      (value "5k1")
      (footprint "eagle-import:R0603")
      (libsource (lib "eagle-import") (part "resistor_348_R-US_R0603"))
    )
    (comp (ref "ROZE1")
      (value "PINHD-1X2")
      (footprint "eagle-import:1X02")
      (libsource (lib "eagle-import") (part "PINHD-1X2"))
    )
    (comp (ref "ROZE2")
      (value "PINHD-1X2")
      (footprint "eagle-import:1X02")
      (libsource (lib "eagle-import") (part "PINHD-1X2"))
    )
    (comp (ref "ROZE3")
      (value "PINHD-1X2")
      (footprint "eagle-import:1X02")
      (libsource (lib "eagle-import") (part "PINHD-1X2"))
    )
    (comp (ref "ROZE4")
      (value "PINHD-1X2")
      (footprint "eagle-import:1X02")
      (libsource (lib "eagle-import") (part "PINHD-1X2"))
    )
    (comp (ref "SWITCH")
      (value "PINHD-1X2")
      (footprint "eagle-import:1X02")
      (libsource (lib "eagle-import") (part "PINHD-1X2"))
    )
    (comp (ref "TCXO")
      (value "OC2E08000XCCDRX")
      (footprint "eagle-import:OC2E08000XCCDRX")
      (libsource (lib "eagle-import") (part "OC2E08000XCCDRX"))
    )
    (comp (ref "U$1")
      (value "VIN-C")
      (footprint "eagle-import:SOLDERING-PAD-4A")
      (libsource (lib "eagle-import") (part "VIAS-CONNECTW1.4MM"))
    )
    (comp (ref "U$2")
      (value "MP5515")
      (footprint "eagle-import:QFN-30")
      (libsource (lib "eagle-import") (part "MP5515"))
    )
    (comp (ref "U$3")
      (value "PCB-\"ARK\"")
      (footprint "eagle-import:ITS-LOGO")
      (libsource (lib "eagle-import") (part "ITS-LOGOPCB-{dblquote}{dblquote}"))
    )
    (comp (ref "U$4")
      (value "PCB-\"ARK\"")
      (footprint "eagle-import:ITS-LOGO")
      (libsource (lib "eagle-import") (part "ITS-LOGOPCB-{dblquote}{dblquote}"))
    )
    (comp (ref "U$5")
      (value "MP5515")
      (footprint "eagle-import:QFN-30")
      (libsource (lib "eagle-import") (part "MP5515"))
    )
    (comp (ref "U$6")
      (value "IRF7329PBF")
      (footprint "eagle-import:SO8")
      (libsource (lib "eagle-import") (part "IRF7329PBF"))
    )
    (comp (ref "U$7")
      (value "GNDS-CONNECTOR")
      (footprint "eagle-import:GNDS-CONNECTOR")
      (libsource (lib "eagle-import") (part "GNDS-CONNECTOR"))
    )
    (comp (ref "U$9")
      (value "VIAS")
      (footprint "eagle-import:VIAS")
      (libsource (lib "eagle-import") (part "VIAS"))
    )
    (comp (ref "U$10")
      (value "IN-")
      (footprint "eagle-import:VIAS")
      (libsource (lib "eagle-import") (part "VIAS"))
    )
    (comp (ref "U$11")
      (value "VIAS")
      (footprint "eagle-import:VIAS")
      (libsource (lib "eagle-import") (part "VIAS"))
    )
    (comp (ref "U$12")
      (value "FFC-CONNECT68611")
      (footprint "eagle-import:68611")
      (libsource (lib "eagle-import") (part "FFC-CONNECT68611"))
    )
    (comp (ref "U$13")
      (value "OUT")
      (footprint "eagle-import:VIAS-CONNECT")
      (libsource (lib "eagle-import") (part "VIAS-CONNECT"))
    )
    (comp (ref "U$14")
      (value "BMS+")
      (footprint "eagle-import:VIAS-CONNECT")
      (libsource (lib "eagle-import") (part "VIAS-CONNECT"))
    )
    (comp (ref "U$15")
      (value "BUS+")
      (footprint "eagle-import:VIAS-CONNECT")
      (libsource (lib "eagle-import") (part "VIAS-CONNECT"))
    )
    (comp (ref "U$16")
      (value "AGND")
      (footprint "eagle-import:VIAS-CONNECT")
      (libsource (lib "eagle-import") (part "VIAS-CONNECT"))
    )
    (comp (ref "U$17")
      (value "VIAS")
      (footprint "eagle-import:VIAS")
      (libsource (lib "eagle-import") (part "VIAS"))
    )
    (comp (ref "U$18")
      (value "VIAS")
      (footprint "eagle-import:VIAS")
      (libsource (lib "eagle-import") (part "VIAS"))
    )
    (comp (ref "U$19")
      (value "IN+")
      (footprint "eagle-import:VIAS")
      (libsource (lib "eagle-import") (part "VIAS"))
    )
    (comp (ref "U$20")
      (value "AGND")
      (footprint "eagle-import:VIAS-CONNECT")
      (libsource (lib "eagle-import") (part "VIAS-CONNECT"))
    )
    (comp (ref "U$21")
      (value "BUS+")
      (footprint "eagle-import:VIAS-CONNECT")
      (libsource (lib "eagle-import") (part "VIAS-CONNECT"))
    )
    (comp (ref "U$22")
      (value "VIAS")
      (footprint "eagle-import:VIAS")
      (libsource (lib "eagle-import") (part "VIAS"))
    )
    (comp (ref "U$23")
      (value "VB-C")
      (footprint "eagle-import:SOLDERING-PAD-4A")
      (libsource (lib "eagle-import") (part "VIAS-CONNECTW1.4MM"))
    )
    (comp (ref "U$24")
      (value "VIAS")
      (footprint "eagle-import:VIAS")
      (libsource (lib "eagle-import") (part "VIAS"))
    )
    (comp (ref "U$25")
      (value "REF")
      (footprint "eagle-import:VIAS")
      (libsource (lib "eagle-import") (part "VIAS"))
    )
    (comp (ref "U$26")
      (value "REF")
      (footprint "eagle-import:VIAS-CONNECT")
      (libsource (lib "eagle-import") (part "VIAS-CONNECT"))
    )
    (comp (ref "U$27")
      (value "VIAS")
      (footprint "eagle-import:VIAS")
      (libsource (lib "eagle-import") (part "VIAS"))
    )
    (comp (ref "U$28")
      (value "IN-")
      (footprint "eagle-import:VIAS")
      (libsource (lib "eagle-import") (part "VIAS"))
    )
    (comp (ref "U$29")
      (value "OUT")
      (footprint "eagle-import:VIAS-CONNECT")
      (libsource (lib "eagle-import") (part "VIAS-CONNECT"))
    )
    (comp (ref "U$30")
      (value "VIAS")
      (footprint "eagle-import:VIAS")
      (libsource (lib "eagle-import") (part "VIAS"))
    )
    (comp (ref "U$31")
      (value "3V3")
      (footprint "eagle-import:VIAS")
      (libsource (lib "eagle-import") (part "VIAS"))
    )
    (comp (ref "U$32")
      (value "IN+")
      (footprint "eagle-import:VIAS")
      (libsource (lib "eagle-import") (part "VIAS"))
    )
    (comp (ref "U$33")
      (value "AGND")
      (footprint "eagle-import:VIAS")
      (libsource (lib "eagle-import") (part "VIAS"))
    )
    (comp (ref "U$34")
      (value "IRF7329PBF")
      (footprint "eagle-import:SO8")
      (libsource (lib "eagle-import") (part "IRF7329PBF"))
    )
    (comp (ref "U$35")
      (value "IRF7329PBF")
      (footprint "eagle-import:SO8")
      (libsource (lib "eagle-import") (part "IRF7329PBF"))
    )
    (comp (ref "U$36")
      (value "IRF7905PBF")
      (footprint "eagle-import:SO8")
      (libsource (lib "eagle-import") (part "IRF7905PBF"))
    )
    (comp (ref "U$37")
      (value "IRF7905PBF")
      (footprint "eagle-import:SO8")
      (libsource (lib "eagle-import") (part "IRF7905PBF"))
    )
    (comp (ref "U$38")
      (value "SI2302CDS")
      (footprint "eagle-import:SOT23-3")
      (libsource (lib "eagle-import") (part "SI2302CDS"))
    )
    (comp (ref "U$39")
      (value "AGND")
      (footprint "eagle-import:VIAS-CONNECT")
      (libsource (lib "eagle-import") (part "VIAS-CONNECT"))
    )
    (comp (ref "U$40")
      (value "3V3")
      (footprint "eagle-import:VIAS-CONNECT")
      (libsource (lib "eagle-import") (part "VIAS-CONNECT"))
    )
    (comp (ref "U$41")
      (value "VIAS")
      (footprint "eagle-import:VIAS")
      (libsource (lib "eagle-import") (part "VIAS"))
    )
    (comp (ref "U$42")
      (value "VIAS")
      (footprint "eagle-import:VIAS")
      (libsource (lib "eagle-import") (part "VIAS"))
    )
    (comp (ref "U$43")
      (value "REF")
      (footprint "eagle-import:VIAS")
      (libsource (lib "eagle-import") (part "VIAS"))
    )
    (comp (ref "U$44")
      (value "AGND")
      (footprint "eagle-import:VIAS-CONNECT")
      (libsource (lib "eagle-import") (part "VIAS-CONNECT"))
    )
    (comp (ref "U$45")
      (value "BUS+")
      (footprint "eagle-import:VIAS-CONNECT")
      (libsource (lib "eagle-import") (part "VIAS-CONNECT"))
    )
    (comp (ref "U$46")
      (value "VIAS")
      (footprint "eagle-import:VIAS")
      (libsource (lib "eagle-import") (part "VIAS"))
    )
    (comp (ref "U$47")
      (value "VIAS")
      (footprint "eagle-import:VIAS")
      (libsource (lib "eagle-import") (part "VIAS"))
    )
    (comp (ref "U$48")
      (value "IN-")
      (footprint "eagle-import:VIAS")
      (libsource (lib "eagle-import") (part "VIAS"))
    )
    (comp (ref "U$49")
      (value "OUT-D")
      (footprint "eagle-import:VIAS-CONNECT")
      (libsource (lib "eagle-import") (part "VIAS-CONNECT"))
    )
    (comp (ref "U$50")
      (value "VIAS")
      (footprint "eagle-import:VIAS")
      (libsource (lib "eagle-import") (part "VIAS"))
    )
    (comp (ref "U$51")
      (value "IN+")
      (footprint "eagle-import:VIAS")
      (libsource (lib "eagle-import") (part "VIAS"))
    )
    (comp (ref "U$52")
      (value "REF")
      (footprint "eagle-import:VIAS-CONNECT")
      (libsource (lib "eagle-import") (part "VIAS-CONNECT"))
    )
    (comp (ref "U$53")
      (value "VIAS")
      (footprint "eagle-import:VIAS")
      (libsource (lib "eagle-import") (part "VIAS"))
    )
    (comp (ref "U$54")
      (value "VIN-D")
      (footprint "eagle-import:SOLDERING-PAD-4A")
      (libsource (lib "eagle-import") (part "VIAS-CONNECTW1.4MM"))
    )
    (comp (ref "U$55")
      (value "VB-D")
      (footprint "eagle-import:SOLDERING-PAD-4A")
      (libsource (lib "eagle-import") (part "VIAS-CONNECTW1.4MM"))
    )
  )
  (nets
    (net (code "1") (name "/0V8") (class "Default")
      (node (ref "3362P") (pin "2") (pinfunction "WIPER_2") (pintype "passive"))
      (node (ref "OPA2") (pin "P$3") (pinfunction "IN+_P$3") (pintype "bidirectional"))
      (node (ref "U$32") (pin "P$1") (pinfunction "1_P$1") (pintype "passive"))
    )
    (net (code "2") (name "/1W") (class "Default")
      (node (ref "IC2") (pin "14") (pinfunction "PA4_14") (pintype "bidirectional"))
      (node (ref "JP1") (pin "7") (pinfunction "7_7") (pintype "passive"))
    )
    (net (code "3") (name "/3V3") (class "Default")
      (node (ref "C16") (pin "1") (pinfunction "1_1") (pintype "passive"))
      (node (ref "C2") (pin "2") (pinfunction "2_2") (pintype "passive"))
      (node (ref "C4") (pin "P+") (pinfunction "1_P+") (pintype "passive"))
      (node (ref "C5") (pin "1") (pinfunction "1_1") (pintype "passive"))
      (node (ref "C6") (pin "1") (pinfunction "1_1") (pintype "passive"))
      (node (ref "C7") (pin "1") (pinfunction "1_1") (pintype "passive"))
      (node (ref "C8") (pin "1") (pinfunction "1_1") (pintype "passive"))
      (node (ref "IC2") (pin "1") (pinfunction "VBAT_1") (pintype "power_in"))
      (node (ref "IC2") (pin "24") (pinfunction "VDD_24") (pintype "bidirectional"))
      (node (ref "IC2") (pin "36") (pinfunction "VDD_36") (pintype "bidirectional"))
      (node (ref "IC2") (pin "48") (pinfunction "VDD_48") (pintype "bidirectional"))
      (node (ref "IC2") (pin "9") (pinfunction "VDDA_9") (pintype "power_in"))
      (node (ref "INA219#1") (pin "4") (pinfunction "VS_4") (pintype "bidirectional"))
      (node (ref "INA219#2") (pin "4") (pinfunction "VS_4") (pintype "bidirectional"))
      (node (ref "INA219#2") (pin "7") (pinfunction "A0_7") (pintype "bidirectional"))
      (node (ref "INVERT1") (pin "P$5") (pinfunction "VCC_P$5") (pintype "bidirectional"))
      (node (ref "LD1117S33") (pin "P$3") (pinfunction "VOUT_P$3") (pintype "bidirectional"))
      (node (ref "LED") (pin "A") (pinfunction "A_A") (pintype "passive"))
      (node (ref "OPA1") (pin "P$5") (pinfunction "V+_P$5") (pintype "bidirectional"))
      (node (ref "OPA2") (pin "P$5") (pinfunction "V+_P$5") (pintype "bidirectional"))
      (node (ref "OPA3") (pin "P$5") (pinfunction "V+_P$5") (pintype "bidirectional"))
      (node (ref "PWR") (pin "A") (pinfunction "A_A") (pintype "passive"))
      (node (ref "R101") (pin "1") (pinfunction "1_1") (pintype "passive"))
      (node (ref "R102") (pin "1") (pinfunction "1_1") (pintype "passive"))
      (node (ref "R11") (pin "2") (pinfunction "2_2") (pintype "passive"))
      (node (ref "R2") (pin "2") (pinfunction "2_2") (pintype "passive"))
      (node (ref "R27") (pin "1") (pinfunction "1_1") (pintype "passive"))
      (node (ref "R49") (pin "2") (pinfunction "2_2") (pintype "passive"))
      (node (ref "R6") (pin "2") (pinfunction "2_2") (pintype "passive"))
      (node (ref "R64") (pin "1") (pinfunction "1_1") (pintype "passive"))
      (node (ref "R79") (pin "1") (pinfunction "1_1") (pintype "passive"))
      (node (ref "R8") (pin "2") (pinfunction "2_2") (pintype "passive"))
      (node (ref "TCXO") (pin "P$1") (pinfunction "EN/DIS_P$1") (pintype "bidirectional"))
      (node (ref "TCXO") (pin "P$4") (pinfunction "VCC_P$4") (pintype "bidirectional"))
      (node (ref "U$12") (pin "P$1") (pinfunction "1_P$1") (pintype "passive"))
      (node (ref "U$12") (pin "P$2") (pinfunction "2_P$2") (pintype "passive"))
      (node (ref "U$31") (pin "P$1") (pinfunction "1_P$1") (pintype "passive"))
      (node (ref "U$40") (pin "1") (pinfunction "1_1") (pintype "passive"))
    )
    (net (code "4") (name "/A") (class "Default")
      (node (ref "INVERT1") (pin "P$2") (pinfunction "A_P$2") (pintype "bidirectional"))
      (node (ref "OPA1") (pin "P$1") (pinfunction "OUT_P$1") (pintype "bidirectional"))
      (node (ref "R38") (pin "2") (pinfunction "2_2") (pintype "passive"))
      (node (ref "U$49") (pin "1") (pinfunction "1_1") (pintype "passive"))
    )
    (net (code "5") (name "/AGND") (class "Default")
      (node (ref "C3.C") (pin "2") (pinfunction "2_2") (pintype "passive"))
      (node (ref "C3.D") (pin "2") (pinfunction "2_2") (pintype "passive"))
      (node (ref "C6.C") (pin "2") (pinfunction "2_2") (pintype "passive"))
      (node (ref "C6.D") (pin "2") (pinfunction "2_2") (pintype "passive"))
      (node (ref "C7.C") (pin "2") (pinfunction "2_2") (pintype "passive"))
      (node (ref "C7.D") (pin "2") (pinfunction "2_2") (pintype "passive"))
      (node (ref "C8.C") (pin "2") (pinfunction "2_2") (pintype "passive"))
      (node (ref "C8.D") (pin "2") (pinfunction "2_2") (pintype "passive"))
      (node (ref "INVERT1") (pin "P$3") (pinfunction "GND_P$3") (pintype "bidirectional"))
      (node (ref "OPA1") (pin "P$2") (pinfunction "V-_P$2") (pintype "bidirectional"))
      (node (ref "OPA2") (pin "P$2") (pinfunction "V-_P$2") (pintype "bidirectional"))
      (node (ref "OPA3") (pin "P$2") (pinfunction "V-_P$2") (pintype "bidirectional"))
      (node (ref "R10.C") (pin "2") (pinfunction "2_2") (pintype "passive"))
      (node (ref "R10.D") (pin "2") (pinfunction "2_2") (pintype "passive"))
      (node (ref "R12") (pin "1") (pinfunction "1_1") (pintype "passive"))
      (node (ref "R13.C") (pin "1") (pinfunction "1_1") (pintype "passive"))
      (node (ref "R13.D") (pin "1") (pinfunction "1_1") (pintype "passive"))
      (node (ref "R18.C") (pin "2") (pinfunction "2_2") (pintype "passive"))
      (node (ref "R18.D") (pin "2") (pinfunction "2_2") (pintype "passive"))
      (node (ref "R19.C") (pin "2") (pinfunction "2_2") (pintype "passive"))
      (node (ref "R19.D") (pin "2") (pinfunction "2_2") (pintype "passive"))
      (node (ref "R2.C") (pin "2") (pinfunction "2_2") (pintype "passive"))
      (node (ref "R2.D") (pin "2") (pinfunction "2_2") (pintype "passive"))
      (node (ref "R6.C") (pin "2") (pinfunction "2_2") (pintype "passive"))
      (node (ref "R6.D") (pin "2") (pinfunction "2_2") (pintype "passive"))
      (node (ref "R7.C") (pin "1") (pinfunction "1_1") (pintype "passive"))
      (node (ref "R7.D") (pin "1") (pinfunction "1_1") (pintype "passive"))
      (node (ref "U$16") (pin "1") (pinfunction "1_1") (pintype "passive"))
      (node (ref "U$2") (pin "9") (pinfunction "AGND_9") (pintype "bidirectional"))
      (node (ref "U$20") (pin "2") (pinfunction "2_2") (pintype "passive"))
      (node (ref "U$33") (pin "P$1") (pinfunction "1_P$1") (pintype "passive"))
      (node (ref "U$39") (pin "2") (pinfunction "2_2") (pintype "passive"))
      (node (ref "U$44") (pin "2") (pinfunction "2_2") (pintype "passive"))
      (node (ref "U$5") (pin "9") (pinfunction "AGND_9") (pintype "bidirectional"))
      (node (ref "U$7") (pin "P$2") (pinfunction "P$2_P$2") (pintype "bidirectional"))
    )
    (net (code "6") (name "/BMS+") (class "Default")
      (node (ref "C11") (pin "P+") (pinfunction "1_P+") (pintype "passive"))
      (node (ref "LD1117S33") (pin "P$4") (pinfunction "VIN_P$4") (pintype "bidirectional"))
      (node (ref "R75") (pin "2") (pinfunction "2_2") (pintype "passive"))
      (node (ref "R76") (pin "1") (pinfunction "1_1") (pintype "passive"))
      (node (ref "SWITCH") (pin "2") (pinfunction "2_2") (pintype "passive"))
      (node (ref "U$14") (pin "1") (pinfunction "1_1") (pintype "passive"))
    )
    (net (code "7") (name "/BMS+_OUT") (class "Default")
      (node (ref "JP1") (pin "8") (pinfunction "8_8") (pintype "passive"))
      (node (ref "SWITCH") (pin "1") (pinfunction "1_1") (pintype "passive"))
    )
    (net (code "8") (name "/BMS1") (class "Default")
      (node (ref "IC2") (pin "11") (pinfunction "PA1_11") (pintype "bidirectional"))
      (node (ref "JP1") (pin "1") (pinfunction "1_1") (pintype "passive"))
    )
    (net (code "9") (name "/BMS2") (class "Default")
      (node (ref "IC2") (pin "12") (pinfunction "PA2_12") (pintype "bidirectional"))
      (node (ref "JP1") (pin "2") (pinfunction "2_2") (pintype "passive"))
    )
    (net (code "10") (name "/BMS3") (class "Default")
      (node (ref "IC2") (pin "4") (pinfunction "PC15_4") (pintype "bidirectional"))
      (node (ref "JP1") (pin "3") (pinfunction "3_3") (pintype "passive"))
    )
    (net (code "11") (name "/BMS4") (class "Default")
      (node (ref "IC2") (pin "10") (pinfunction "PA0-WKUP_10") (pintype "bidirectional"))
      (node (ref "JP1") (pin "4") (pinfunction "4_4") (pintype "passive"))
    )
    (net (code "12") (name "/BMS5") (class "Default")
      (node (ref "IC2") (pin "2") (pinfunction "PC13_2") (pintype "bidirectional"))
      (node (ref "JP1") (pin "5") (pinfunction "5_5") (pintype "passive"))
    )
    (net (code "13") (name "/BMS6") (class "Default")
      (node (ref "IC2") (pin "3") (pinfunction "PC14_3") (pintype "bidirectional"))
      (node (ref "JP1") (pin "6") (pinfunction "6_6") (pintype "passive"))
    )
    (net (code "14") (name "/BUS+") (class "Default")
      (node (ref "JP1") (pin "16") (pinfunction "16_16") (pintype "passive"))
      (node (ref "R71") (pin "2") (pinfunction "2_2") (pintype "passive"))
      (node (ref "R73") (pin "1") (pinfunction "1_1") (pintype "passive"))
      (node (ref "U$15") (pin "2") (pinfunction "2_2") (pintype "passive"))
      (node (ref "U$21") (pin "1") (pinfunction "1_1") (pintype "passive"))
      (node (ref "U$45") (pin "1") (pinfunction "1_1") (pintype "passive"))
    )
    (net (code "15") (name "/C-OFF") (class "Default")
      (node (ref "IC2") (pin "19") (pinfunction "PB1_19") (pintype "bidirectional"))
      (node (ref "R3") (pin "1") (pinfunction "1_1") (pintype "passive"))
    )
    (net (code "16") (name "/D-OFF") (class "Default")
      (node (ref "IC2") (pin "20") (pinfunction "PB2_20") (pintype "bidirectional"))
      (node (ref "R39") (pin "2") (pinfunction "2_2") (pintype "passive"))
    )
    (net (code "17") (name "/DC-DC") (class "Default")
      (node (ref "IC2") (pin "38") (pinfunction "PA15_38") (pintype "bidirectional"))
      (node (ref "R42") (pin "2") (pinfunction "2_2") (pintype "passive"))
      (node (ref "U$38") (pin "1") (pinfunction "G_1") (pintype "bidirectional"))
    )
    (net (code "18") (name "/FBB-C") (class "Default")
      (node (ref "R15") (pin "2") (pinfunction "2_2") (pintype "passive"))
      (node (ref "U$2") (pin "22") (pinfunction "FBB_22") (pintype "bidirectional"))
    )
    (net (code "19") (name "/FBB-D") (class "Default")
      (node (ref "R25") (pin "2") (pinfunction "2_2") (pintype "passive"))
      (node (ref "U$5") (pin "22") (pinfunction "FBB_22") (pintype "bidirectional"))
    )
    (net (code "20") (name "/GND") (class "Default")
      (node (ref "C1.C") (pin "1") (pinfunction "1_1") (pintype "passive"))
      (node (ref "C1.D") (pin "1") (pinfunction "1_1") (pintype "passive"))
      (node (ref "C11") (pin "P-") (pinfunction "2_P-") (pintype "passive"))
      (node (ref "C16") (pin "2") (pinfunction "2_2") (pintype "passive"))
      (node (ref "C2") (pin "1") (pinfunction "1_1") (pintype "passive"))
      (node (ref "C2A.C") (pin "2") (pinfunction "2_2") (pintype "passive"))
      (node (ref "C2A.D") (pin "2") (pinfunction "2_2") (pintype "passive"))
      (node (ref "C2B.C") (pin "2") (pinfunction "2_2") (pintype "passive"))
      (node (ref "C2B.D") (pin "2") (pinfunction "2_2") (pintype "passive"))
      (node (ref "C4") (pin "P-") (pinfunction "2_P-") (pintype "passive"))
      (node (ref "C4A.C") (pin "1") (pinfunction "1_1") (pintype "passive"))
      (node (ref "C4A.D") (pin "1") (pinfunction "1_1") (pintype "passive"))
      (node (ref "C4B.C") (pin "P$2") (pinfunction "2_P$2") (pintype "passive"))
      (node (ref "C4B.D") (pin "P$2") (pinfunction "2_P$2") (pintype "passive"))
      (node (ref "C5") (pin "2") (pinfunction "2_2") (pintype "passive"))
      (node (ref "C6") (pin "2") (pinfunction "2_2") (pintype "passive"))
      (node (ref "C7") (pin "2") (pinfunction "2_2") (pintype "passive"))
      (node (ref "C8") (pin "2") (pinfunction "2_2") (pintype "passive"))
      (node (ref "D$1") (pin "P$1") (pinfunction "A_P$1") (pintype "passive"))
      (node (ref "D$2") (pin "P$1") (pinfunction "A_P$1") (pintype "passive"))
      (node (ref "IC2") (pin "23") (pinfunction "VSSA_23") (pintype "power_in"))
      (node (ref "IC2") (pin "35") (pinfunction "VSSA_35") (pintype "power_in"))
      (node (ref "IC2") (pin "44") (pinfunction "BOOT0_44") (pintype "input"))
      (node (ref "IC2") (pin "47") (pinfunction "VSSA_47") (pintype "power_in"))
      (node (ref "IC2") (pin "8") (pinfunction "VSSA_8") (pintype "power_in"))
      (node (ref "INA219#1") (pin "3") (pinfunction "GND_3") (pintype "bidirectional"))
      (node (ref "INA219#1") (pin "7") (pinfunction "A0_7") (pintype "bidirectional"))
      (node (ref "INA219#1") (pin "8") (pinfunction "A1_8") (pintype "bidirectional"))
      (node (ref "INA219#2") (pin "3") (pinfunction "GND_3") (pintype "bidirectional"))
      (node (ref "INA219#2") (pin "8") (pinfunction "A1_8") (pintype "bidirectional"))
      (node (ref "JP1") (pin "11") (pinfunction "11_11") (pintype "passive"))
      (node (ref "JP1") (pin "12") (pinfunction "12_12") (pintype "passive"))
      (node (ref "LD1117S33") (pin "P$2") (pinfunction "GND_P$2") (pintype "bidirectional"))
      (node (ref "R16") (pin "1") (pinfunction "1_1") (pintype "passive"))
      (node (ref "R17") (pin "1") (pinfunction "1_1") (pintype "passive"))
      (node (ref "R18") (pin "1") (pinfunction "1_1") (pintype "passive"))
      (node (ref "R23") (pin "1") (pinfunction "1_1") (pintype "passive"))
      (node (ref "R24") (pin "1") (pinfunction "1_1") (pintype "passive"))
      (node (ref "R26") (pin "1") (pinfunction "1_1") (pintype "passive"))
      (node (ref "R42") (pin "1") (pinfunction "1_1") (pintype "passive"))
      (node (ref "R82") (pin "1") (pinfunction "1_1") (pintype "passive"))
      (node (ref "ROZE1") (pin "2") (pinfunction "2_2") (pintype "passive"))
      (node (ref "ROZE2") (pin "2") (pinfunction "2_2") (pintype "passive"))
      (node (ref "ROZE3") (pin "2") (pinfunction "2_2") (pintype "passive"))
      (node (ref "ROZE4") (pin "2") (pinfunction "2_2") (pintype "passive"))
      (node (ref "TCXO") (pin "P$2") (pinfunction "GND_P$2") (pintype "bidirectional"))
      (node (ref "U$12") (pin "P$3") (pinfunction "3_P$3") (pintype "passive"))
      (node (ref "U$12") (pin "P$5") (pinfunction "5_P$5") (pintype "passive"))
      (node (ref "U$12") (pin "P$7") (pinfunction "7_P$7") (pintype "passive"))
      (node (ref "U$12") (pin "P$9") (pinfunction "9_P$9") (pintype "passive"))
      (node (ref "U$2") (pin "28") (pinfunction "PGND_28") (pintype "bidirectional"))
      (node (ref "U$36") (pin "1") (pinfunction "S2_1") (pintype "passive"))
      (node (ref "U$36") (pin "3") (pinfunction "S1_3") (pintype "passive"))
      (node (ref "U$37") (pin "1") (pinfunction "S2_1") (pintype "passive"))
      (node (ref "U$37") (pin "3") (pinfunction "S1_3") (pintype "passive"))
      (node (ref "U$38") (pin "2") (pinfunction "S_2") (pintype "bidirectional"))
      (node (ref "U$5") (pin "28") (pinfunction "PGND_28") (pintype "bidirectional"))
      (node (ref "U$7") (pin "P$1") (pinfunction "P$1_P$1") (pintype "bidirectional"))
    )
    (net (code "21") (name "/INA_BMS+") (class "Default")
      (node (ref "R34") (pin "1") (pinfunction "1_1") (pintype "passive"))
      (node (ref "R40") (pin "1") (pinfunction "1_1") (pintype "passive"))
      (node (ref "R75") (pin "1") (pinfunction "1_1") (pintype "passive"))
      (node (ref "R77") (pin "1") (pinfunction "1_1") (pintype "passive"))
      (node (ref "U$34") (pin "3") (pinfunction "S2_3") (pintype "passive"))
      (node (ref "U$35") (pin "3") (pinfunction "S2_3") (pintype "passive"))
      (node (ref "U$6") (pin "7") (pinfunction "D1_7") (pintype "passive"))
      (node (ref "U$6") (pin "8") (pinfunction "D1_8") (pintype "passive"))
    )
    (net (code "22") (name "/INA_BUS+") (class "Default")
      (node (ref "R29") (pin "1") (pinfunction "1_1") (pintype "passive"))
      (node (ref "R41") (pin "1") (pinfunction "1_1") (pintype "passive"))
      (node (ref "R71") (pin "1") (pinfunction "1_1") (pintype "passive"))
      (node (ref "R74") (pin "1") (pinfunction "1_1") (pintype "passive"))
      (node (ref "U$34") (pin "7") (pinfunction "D1_7") (pintype "passive"))
      (node (ref "U$34") (pin "8") (pinfunction "D1_8") (pintype "passive"))
      (node (ref "U$35") (pin "1") (pinfunction "S1_1") (pintype "passive"))
      (node (ref "U$6") (pin "3") (pinfunction "S2_3") (pintype "passive"))
    )
    (net (code "23") (name "/INT-C") (class "Default")
      (node (ref "IC2") (pin "26") (pinfunction "PB13_26") (pintype "bidirectional"))
      (node (ref "R15.C") (pin "1") (pinfunction "1_1") (pintype "passive"))
      (node (ref "U$2") (pin "17") (pinfunction "INT_17") (pintype "bidirectional"))
    )
    (net (code "24") (name "/INT-D") (class "Default")
      (node (ref "IC2") (pin "41") (pinfunction "PB5_41") (pintype "bidirectional"))
      (node (ref "R15.D") (pin "1") (pinfunction "1_1") (pintype "passive"))
      (node (ref "U$5") (pin "17") (pinfunction "INT_17") (pintype "bidirectional"))
    )
    (net (code "25") (name "/LED") (class "Default")
      (node (ref "IC2") (pin "25") (pinfunction "PB12_25") (pintype "bidirectional"))
      (node (ref "R81") (pin "1") (pinfunction "1_1") (pintype "passive"))
    )
    (net (code "26") (name "/NRST") (class "Default")
      (node (ref "IC2") (pin "7") (pinfunction "NRST_7") (pintype "bidirectional"))
      (node (ref "R79") (pin "2") (pinfunction "2_2") (pintype "passive"))
      (node (ref "U$12") (pin "P$11") (pinfunction "11_P$11") (pintype "passive"))
    )
    (net (code "27") (name "/PFI-C") (class "Default")
      (node (ref "IC2") (pin "29") (pinfunction "PA8_29") (pintype "bidirectional"))
      (node (ref "PFI-C") (pin "A") (pinfunction "A_A") (pintype "passive"))
      (node (ref "R14.C") (pin "2") (pinfunction "2_2") (pintype "passive"))
      (node (ref "U$2") (pin "6") (pinfunction "PFI_6") (pintype "bidirectional"))
    )
    (net (code "28") (name "/PFI-D") (class "Default")
      (node (ref "IC2") (pin "40") (pinfunction "PB4_40") (pintype "bidirectional"))
      (node (ref "PFI-D") (pin "A") (pinfunction "A_A") (pintype "passive"))
      (node (ref "R14.D") (pin "2") (pinfunction "2_2") (pintype "passive"))
      (node (ref "U$5") (pin "6") (pinfunction "PFI_6") (pintype "bidirectional"))
    )
    (net (code "29") (name "/PGB-C") (class "Default")
      (node (ref "IC2") (pin "27") (pinfunction "PB14_27") (pintype "bidirectional"))
      (node (ref "PGB-C") (pin "A") (pinfunction "A_A") (pintype "passive"))
      (node (ref "U$2") (pin "16") (pinfunction "PGB_16") (pintype "bidirectional"))
    )
    (net (code "30") (name "/PGB-D") (class "Default")
      (node (ref "IC2") (pin "42") (pinfunction "PB6_42") (pintype "bidirectional"))
      (node (ref "PGB-D") (pin "A") (pinfunction "A_A") (pintype "passive"))
      (node (ref "U$5") (pin "16") (pinfunction "PGB_16") (pintype "bidirectional"))
    )
    (net (code "31") (name "/PGS-C") (class "Default")
      (node (ref "IC2") (pin "28") (pinfunction "PB15_28") (pintype "bidirectional"))
      (node (ref "PGS-C") (pin "A") (pinfunction "A_A") (pintype "passive"))
      (node (ref "U$2") (pin "15") (pinfunction "PGS_15") (pintype "bidirectional"))
    )
    (net (code "32") (name "/PGS-D") (class "Default")
      (node (ref "IC2") (pin "43") (pinfunction "PB7_43") (pintype "bidirectional"))
      (node (ref "PGS-D") (pin "A") (pinfunction "A_A") (pintype "passive"))
      (node (ref "U$5") (pin "15") (pinfunction "PGS_15") (pintype "bidirectional"))
    )
    (net (code "33") (name "/ROZE-1") (class "Default")
      (node (ref "IC2") (pin "15") (pinfunction "PA5_15") (pintype "bidirectional"))
      (node (ref "R2") (pin "1") (pinfunction "1_1") (pintype "passive"))
      (node (ref "ROZE1") (pin "1") (pinfunction "1_1") (pintype "passive"))
    )
    (net (code "34") (name "/ROZE-2") (class "Default")
      (node (ref "IC2") (pin "16") (pinfunction "PA6_16") (pintype "bidirectional"))
      (node (ref "R6") (pin "1") (pinfunction "1_1") (pintype "passive"))
      (node (ref "ROZE2") (pin "1") (pinfunction "1_1") (pintype "passive"))
    )
    (net (code "35") (name "/ROZE-3") (class "Default")
      (node (ref "IC2") (pin "17") (pinfunction "PA7_17") (pintype "bidirectional"))
      (node (ref "R8") (pin "1") (pinfunction "1_1") (pintype "passive"))
      (node (ref "ROZE3") (pin "1") (pinfunction "1_1") (pintype "passive"))
    )
    (net (code "36") (name "/ROZE-4") (class "Default")
      (node (ref "IC2") (pin "18") (pinfunction "PB0_18") (pintype "bidirectional"))
      (node (ref "R49") (pin "1") (pinfunction "1_1") (pintype "passive"))
      (node (ref "ROZE4") (pin "1") (pinfunction "1_1") (pintype "passive"))
    )
    (net (code "37") (name "/RX-S") (class "Default")
      (node (ref "IC2") (pin "31") (pinfunction "PA10_31") (pintype "bidirectional"))
      (node (ref "U$12") (pin "P$4") (pinfunction "4_P$4") (pintype "passive"))
    )
    (net (code "38") (name "/SCL") (class "Default")
      (node (ref "IC2") (pin "21") (pinfunction "PB10_21") (pintype "bidirectional"))
      (node (ref "INA219#1") (pin "5") (pinfunction "SCL_5") (pintype "bidirectional"))
      (node (ref "INA219#2") (pin "5") (pinfunction "SCL_5") (pintype "bidirectional"))
      (node (ref "R101") (pin "2") (pinfunction "2_2") (pintype "passive"))
    )
    (net (code "39") (name "/SCLTM") (class "Default")
      (node (ref "IC2") (pin "45") (pinfunction "PB8_45") (pintype "bidirectional"))
      (node (ref "JP1") (pin "13") (pinfunction "13_13") (pintype "passive"))
    )
    (net (code "40") (name "/SDA") (class "Default")
      (node (ref "IC2") (pin "22") (pinfunction "PB11_22") (pintype "bidirectional"))
      (node (ref "INA219#1") (pin "6") (pinfunction "SDA_6") (pintype "bidirectional"))
      (node (ref "INA219#2") (pin "6") (pinfunction "SDA_6") (pintype "bidirectional"))
      (node (ref "R102") (pin "2") (pinfunction "2_2") (pintype "passive"))
    )
    (net (code "41") (name "/SDATM") (class "Default")
      (node (ref "IC2") (pin "46") (pinfunction "PB9_46") (pintype "bidirectional"))
      (node (ref "JP1") (pin "14") (pinfunction "14_14") (pintype "passive"))
    )
    (net (code "42") (name "/SWC") (class "Default")
      (node (ref "IC2") (pin "37") (pinfunction "PA14_37") (pintype "bidirectional"))
      (node (ref "R27") (pin "2") (pinfunction "2_2") (pintype "passive"))
      (node (ref "U$12") (pin "P$10") (pinfunction "10_P$10") (pintype "passive"))
    )
    (net (code "43") (name "/SWD") (class "Default")
      (node (ref "IC2") (pin "34") (pinfunction "PA13_34") (pintype "bidirectional"))
      (node (ref "R64") (pin "2") (pinfunction "2_2") (pintype "passive"))
      (node (ref "U$12") (pin "P$8") (pinfunction "8_P$8") (pintype "passive"))
    )
    (net (code "44") (name "/TIME") (class "Default")
      (node (ref "IC2") (pin "13") (pinfunction "PA3_13") (pintype "bidirectional"))
      (node (ref "JP1") (pin "15") (pinfunction "15_15") (pintype "passive"))
    )
    (net (code "45") (name "/TX-S") (class "Default")
      (node (ref "IC2") (pin "30") (pinfunction "PA9_30") (pintype "bidirectional"))
      (node (ref "U$12") (pin "P$6") (pinfunction "6_P$6") (pintype "passive"))
    )
    (net (code "46") (name "/VB-C") (class "Default")
      (node (ref "C2A.C") (pin "1") (pinfunction "1_1") (pintype "passive"))
      (node (ref "C2B.C") (pin "1") (pinfunction "1_1") (pintype "passive"))
      (node (ref "R12.C") (pin "1") (pinfunction "1_1") (pintype "passive"))
      (node (ref "U$2") (pin "12") (pinfunction "VB_12") (pintype "bidirectional"))
      (node (ref "U$2") (pin "29") (pinfunction "VB_29") (pintype "bidirectional"))
      (node (ref "U$23") (pin "P$2") (pinfunction "2_P$2") (pintype "passive"))
    )
    (net (code "47") (name "/VB-D") (class "Default")
      (node (ref "C2A.D") (pin "1") (pinfunction "1_1") (pintype "passive"))
      (node (ref "C2B.D") (pin "1") (pinfunction "1_1") (pintype "passive"))
      (node (ref "R12.D") (pin "1") (pinfunction "1_1") (pintype "passive"))
      (node (ref "U$5") (pin "12") (pinfunction "VB_12") (pintype "bidirectional"))
      (node (ref "U$5") (pin "29") (pinfunction "VB_29") (pintype "bidirectional"))
      (node (ref "U$55") (pin "P$2") (pinfunction "2_P$2") (pintype "passive"))
    )
    (net (code "48") (name "/VBO-C") (class "Default")
      (node (ref "L1.C") (pin "P$2") (pinfunction "2_P$2") (pintype "passive"))
      (node (ref "U$2") (pin "14") (pinfunction "VBO_14") (pintype "bidirectional"))
    )
    (net (code "49") (name "/VBO-D") (class "Default")
      (node (ref "L1.D") (pin "P$2") (pinfunction "2_P$2") (pintype "passive"))
      (node (ref "U$5") (pin "14") (pinfunction "VBO_14") (pintype "bidirectional"))
    )
    (net (code "50") (name "/VCC-C") (class "Default")
      (node (ref "C3.C") (pin "1") (pinfunction "1_1") (pintype "passive"))
      (node (ref "R14.C") (pin "1") (pinfunction "1_1") (pintype "passive"))
      (node (ref "R15.C") (pin "2") (pinfunction "2_2") (pintype "passive"))
      (node (ref "R16.C") (pin "2") (pinfunction "2_2") (pintype "passive"))
      (node (ref "R17.C") (pin "2") (pinfunction "2_2") (pintype "passive"))
      (node (ref "U$2") (pin "2") (pinfunction "VCC_2") (pintype "bidirectional"))
    )
    (net (code "51") (name "/VCC-D") (class "Default")
      (node (ref "C3.D") (pin "1") (pinfunction "1_1") (pintype "passive"))
      (node (ref "R14.D") (pin "1") (pinfunction "1_1") (pintype "passive"))
      (node (ref "R15.D") (pin "2") (pinfunction "2_2") (pintype "passive"))
      (node (ref "R16.D") (pin "2") (pinfunction "2_2") (pintype "passive"))
      (node (ref "R17.D") (pin "2") (pinfunction "2_2") (pintype "passive"))
      (node (ref "U$5") (pin "2") (pinfunction "VCC_2") (pintype "bidirectional"))
    )
    (net (code "52") (name "/VIN-C") (class "Default")
      (node (ref "C1.C") (pin "2") (pinfunction "2_2") (pintype "passive"))
      (node (ref "D$1") (pin "P$2") (pinfunction "C_P$2") (pintype "passive"))
      (node (ref "R1.C") (pin "1") (pinfunction "1_1") (pintype "passive"))
      (node (ref "R11.C") (pin "2") (pinfunction "2_2") (pintype "passive"))
      (node (ref "R9.C") (pin "1") (pinfunction "1_1") (pintype "passive"))
      (node (ref "U$1") (pin "P$2") (pinfunction "2_P$2") (pintype "passive"))
      (node (ref "U$2") (pin "11") (pinfunction "VIN_11") (pintype "bidirectional"))
      (node (ref "U$2") (pin "30") (pinfunction "VIN_30") (pintype "bidirectional"))
    )
    (net (code "53") (name "/VIN-D") (class "Default")
      (node (ref "C1.D") (pin "2") (pinfunction "2_2") (pintype "passive"))
      (node (ref "D$2") (pin "P$2") (pinfunction "C_P$2") (pintype "passive"))
      (node (ref "R1.D") (pin "1") (pinfunction "1_1") (pintype "passive"))
      (node (ref "R11.D") (pin "2") (pinfunction "2_2") (pintype "passive"))
      (node (ref "R9.D") (pin "1") (pinfunction "1_1") (pintype "passive"))
      (node (ref "U$5") (pin "11") (pinfunction "VIN_11") (pintype "bidirectional"))
      (node (ref "U$5") (pin "30") (pinfunction "VIN_30") (pintype "bidirectional"))
      (node (ref "U$54") (pin "P$2") (pinfunction "2_P$2") (pintype "passive"))
    )
    (net (code "54") (name "/Y") (class "Default")
      (node (ref "INVERT1") (pin "P$4") (pinfunction "Y_P$4") (pintype "bidirectional"))
      (node (ref "R1") (pin "1") (pinfunction "1_1") (pintype "passive"))
    )
    (net (code "55") (name "Net-(3362P-CCW)") (class "Default")
      (node (ref "3362P") (pin "1") (pinfunction "CCW_1") (pintype "passive"))
      (node (ref "R12") (pin "2") (pinfunction "2_2") (pintype "passive"))
    )
    (net (code "56") (name "Net-(3362P-CW)") (class "Default")
      (node (ref "3362P") (pin "3") (pinfunction "CW_3") (pintype "passive"))
      (node (ref "R11") (pin "1") (pinfunction "1_1") (pintype "passive"))
    )
    (net (code "57") (name "Net-(3362P1-CCW)") (class "Default")
      (node (ref "3362P1") (pin "1") (pinfunction "CCW_1") (pintype "passive"))
      (node (ref "R14") (pin "2") (pinfunction "2_2") (pintype "passive"))
    )
    (net (code "58") (name "Net-(3362P1-CW)") (class "Default")
      (node (ref "3362P1") (pin "3") (pinfunction "CW_3") (pintype "passive"))
      (node (ref "R13") (pin "1") (pinfunction "1_1") (pintype "passive"))
    )
    (net (code "59") (name "Net-(3362P1-WIPER)") (class "Default")
      (node (ref "3362P1") (pin "2") (pinfunction "WIPER_2") (pintype "passive"))
      (node (ref "U$25") (pin "P$1") (pinfunction "1_P$1") (pintype "passive"))
      (node (ref "U$26") (pin "1") (pinfunction "1_1") (pintype "passive"))
    )
    (net (code "60") (name "Net-(3362P2-CCW)") (class "Default")
      (node (ref "3362P2") (pin "1") (pinfunction "CCW_1") (pintype "passive"))
      (node (ref "R21") (pin "2") (pinfunction "2_2") (pintype "passive"))
    )
    (net (code "61") (name "Net-(3362P2-CW)") (class "Default")
      (node (ref "3362P2") (pin "3") (pinfunction "CW_3") (pintype "passive"))
      (node (ref "R20") (pin "1") (pinfunction "1_1") (pintype "passive"))
    )
    (net (code "62") (name "Net-(3362P2-WIPER)") (class "Default")
      (node (ref "3362P2") (pin "2") (pinfunction "WIPER_2") (pintype "passive"))
      (node (ref "OPA3") (pin "P$3") (pinfunction "IN+_P$3") (pintype "bidirectional"))
      (node (ref "U$19") (pin "P$1") (pinfunction "1_P$1") (pintype "passive"))
    )
    (net (code "63") (name "Net-(3362P3-CCW)") (class "Default")
      (node (ref "3362P3") (pin "1") (pinfunction "CCW_1") (pintype "passive"))
      (node (ref "R44") (pin "2") (pinfunction "2_2") (pintype "passive"))
    )
    (net (code "64") (name "Net-(3362P3-CW)") (class "Default")
      (node (ref "3362P3") (pin "3") (pinfunction "CW_3") (pintype "passive"))
      (node (ref "R43") (pin "1") (pinfunction "1_1") (pintype "passive"))
    )
    (net (code "65") (name "Net-(3362P3-WIPER)") (class "Default")
      (node (ref "3362P3") (pin "2") (pinfunction "WIPER_2") (pintype "passive"))
      (node (ref "U$43") (pin "P$1") (pinfunction "1_P$1") (pintype "passive"))
      (node (ref "U$52") (pin "1") (pinfunction "1_1") (pintype "passive"))
    )
    (net (code "66") (name "Net-(3362P4-CCW)") (class "Default")
      (node (ref "3362P4") (pin "1") (pinfunction "CCW_1") (pintype "passive"))
      (node (ref "R22") (pin "1") (pinfunction "1_1") (pintype "passive"))
    )
    (net (code "67") (name "Net-(3362P4-CW)") (class "Default")
      (node (ref "3362P4") (pin "3") (pinfunction "CW_3") (pintype "passive"))
      (node (ref "R19") (pin "2") (pinfunction "2_2") (pintype "passive"))
    )
    (net (code "68") (name "Net-(3362P4-WIPER)") (class "Default")
      (node (ref "3362P4") (pin "2") (pinfunction "WIPER_2") (pintype "passive"))
      (node (ref "OPA3") (pin "P$4") (pinfunction "IN-_P$4") (pintype "bidirectional"))
      (node (ref "U$10") (pin "P$1") (pinfunction "1_P$1") (pintype "passive"))
    )
    (net (code "69") (name "Net-(3362P5-CCW)") (class "Default")
      (node (ref "3362P5") (pin "1") (pinfunction "CCW_1") (pintype "passive"))
      (node (ref "R46") (pin "2") (pinfunction "2_2") (pintype "passive"))
    )
    (net (code "70") (name "Net-(3362P5-CW)") (class "Default")
      (node (ref "3362P5") (pin "3") (pinfunction "CW_3") (pintype "passive"))
      (node (ref "R45") (pin "1") (pinfunction "1_1") (pintype "passive"))
    )
    (net (code "71") (name "Net-(3362P5-WIPER)") (class "Default")
      (node (ref "3362P5") (pin "2") (pinfunction "WIPER_2") (pintype "passive"))
      (node (ref "OPA1") (pin "P$4") (pinfunction "IN-_P$4") (pintype "bidirectional"))
      (node (ref "U$48") (pin "P$1") (pinfunction "1_P$1") (pintype "passive"))
    )
    (net (code "72") (name "Net-(3362P6-CCW)") (class "Default")
      (node (ref "3362P6") (pin "1") (pinfunction "CCW_1") (pintype "passive"))
      (node (ref "R10") (pin "1") (pinfunction "1_1") (pintype "passive"))
    )
    (net (code "73") (name "Net-(3362P6-CW)") (class "Default")
      (node (ref "3362P6") (pin "3") (pinfunction "CW_3") (pintype "passive"))
      (node (ref "R9") (pin "2") (pinfunction "2_2") (pintype "passive"))
    )
    (net (code "74") (name "Net-(3362P6-WIPER)") (class "Default")
      (node (ref "3362P6") (pin "2") (pinfunction "WIPER_2") (pintype "passive"))
      (node (ref "OPA2") (pin "P$4") (pinfunction "IN-_P$4") (pintype "bidirectional"))
      (node (ref "U$28") (pin "P$1") (pinfunction "1_P$1") (pintype "passive"))
    )
    (net (code "75") (name "Net-(3362P7-CCW)") (class "Default")
      (node (ref "3362P7") (pin "1") (pinfunction "CCW_1") (pintype "passive"))
      (node (ref "R48") (pin "1") (pinfunction "1_1") (pintype "passive"))
    )
    (net (code "76") (name "Net-(3362P7-CW)") (class "Default")
      (node (ref "3362P7") (pin "3") (pinfunction "CW_3") (pintype "passive"))
      (node (ref "R47") (pin "2") (pinfunction "2_2") (pintype "passive"))
    )
    (net (code "77") (name "Net-(3362P7-WIPER)") (class "Default")
      (node (ref "3362P7") (pin "2") (pinfunction "WIPER_2") (pintype "passive"))
      (node (ref "OPA1") (pin "P$3") (pinfunction "IN+_P$3") (pintype "bidirectional"))
      (node (ref "U$51") (pin "P$1") (pinfunction "1_P$1") (pintype "passive"))
    )
    (net (code "78") (name "Net-(C4B.C-1)") (class "Default")
      (node (ref "C4A.C") (pin "2") (pinfunction "2_2") (pintype "passive"))
      (node (ref "C4B.C") (pin "P$1") (pinfunction "1_P$1") (pintype "passive"))
      (node (ref "R5.C") (pin "1") (pinfunction "1_1") (pintype "passive"))
      (node (ref "R8.C") (pin "1") (pinfunction "1_1") (pintype "passive"))
      (node (ref "U$2") (pin "26") (pinfunction "STRG_26") (pintype "bidirectional"))
    )
    (net (code "79") (name "Net-(C4B.D-1)") (class "Default")
      (node (ref "C4A.D") (pin "2") (pinfunction "2_2") (pintype "passive"))
      (node (ref "C4B.D") (pin "P$1") (pinfunction "1_P$1") (pintype "passive"))
      (node (ref "R5.D") (pin "1") (pinfunction "1_1") (pintype "passive"))
      (node (ref "R8.D") (pin "1") (pinfunction "1_1") (pintype "passive"))
      (node (ref "U$5") (pin "26") (pinfunction "STRG_26") (pintype "bidirectional"))
    )
    (net (code "80") (name "Net-(IC2-OSC_IN)") (class "Default")
      (node (ref "C1") (pin "1") (pinfunction "1_1") (pintype "passive"))
      (node (ref "IC2") (pin "5") (pinfunction "OSC_IN_5") (pintype "bidirectional"))
    )
    (net (code "81") (name "Net-(INA219#1-IN+)") (class "Default")
      (node (ref "C9") (pin "1") (pinfunction "1_1") (pintype "passive"))
      (node (ref "INA219#1") (pin "1") (pinfunction "IN+_1") (pintype "bidirectional"))
      (node (ref "R73") (pin "2") (pinfunction "2_2") (pintype "passive"))
    )
    (net (code "82") (name "Net-(INA219#1-IN-)") (class "Default")
      (node (ref "C9") (pin "2") (pinfunction "2_2") (pintype "passive"))
      (node (ref "INA219#1") (pin "2") (pinfunction "IN-_2") (pintype "bidirectional"))
      (node (ref "R74") (pin "2") (pinfunction "2_2") (pintype "passive"))
    )
    (net (code "83") (name "Net-(INA219#2-IN+)") (class "Default")
      (node (ref "C10") (pin "1") (pinfunction "1_1") (pintype "passive"))
      (node (ref "INA219#2") (pin "1") (pinfunction "IN+_1") (pintype "bidirectional"))
      (node (ref "R76") (pin "2") (pinfunction "2_2") (pintype "passive"))
    )
    (net (code "84") (name "Net-(INA219#2-IN-)") (class "Default")
      (node (ref "C10") (pin "2") (pinfunction "2_2") (pintype "passive"))
      (node (ref "INA219#2") (pin "2") (pinfunction "IN-_2") (pintype "bidirectional"))
      (node (ref "R77") (pin "2") (pinfunction "2_2") (pintype "passive"))
    )
    (net (code "85") (name "Net-(L1.C-1)") (class "Default")
      (node (ref "C5.C") (pin "1") (pinfunction "1_1") (pintype "passive"))
      (node (ref "L1.C") (pin "P$1") (pinfunction "1_P$1") (pintype "passive"))
      (node (ref "U$2") (pin "27") (pinfunction "SW_27") (pintype "bidirectional"))
    )
    (net (code "86") (name "Net-(L1.D-1)") (class "Default")
      (node (ref "C5.D") (pin "1") (pinfunction "1_1") (pintype "passive"))
      (node (ref "L1.D") (pin "P$1") (pinfunction "1_P$1") (pintype "passive"))
      (node (ref "U$5") (pin "27") (pinfunction "SW_27") (pintype "bidirectional"))
    )
    (net (code "87") (name "Net-(LED-PadC)") (class "Default")
      (node (ref "LED") (pin "C") (pinfunction "C_C") (pintype "passive"))
      (node (ref "R81") (pin "2") (pinfunction "2_2") (pintype "passive"))
    )
    (net (code "88") (name "Net-(OPA2-OUT)") (class "Default")
      (node (ref "OPA2") (pin "P$1") (pinfunction "OUT_P$1") (pintype "bidirectional"))
      (node (ref "R15") (pin "1") (pinfunction "1_1") (pintype "passive"))
      (node (ref "U$29") (pin "1") (pinfunction "1_1") (pintype "passive"))
    )
    (net (code "89") (name "Net-(OPA3-OUT)") (class "Default")
      (node (ref "OPA3") (pin "P$1") (pinfunction "OUT_P$1") (pintype "bidirectional"))
      (node (ref "R25") (pin "1") (pinfunction "1_1") (pintype "passive"))
      (node (ref "U$13") (pin "1") (pinfunction "1_1") (pintype "passive"))
    )
    (net (code "90") (name "Net-(PFI-C-PadC)") (class "Default")
      (node (ref "PFI-C") (pin "C") (pinfunction "C_C") (pintype "passive"))
      (node (ref "R16") (pin "2") (pinfunction "2_2") (pintype "passive"))
    )
    (net (code "91") (name "Net-(PFI-D-PadC)") (class "Default")
      (node (ref "PFI-D") (pin "C") (pinfunction "C_C") (pintype "passive"))
      (node (ref "R23") (pin "2") (pinfunction "2_2") (pintype "passive"))
    )
    (net (code "92") (name "Net-(PGB-C-PadC)") (class "Default")
      (node (ref "PGB-C") (pin "C") (pinfunction "C_C") (pintype "passive"))
      (node (ref "R18") (pin "2") (pinfunction "2_2") (pintype "passive"))
    )
    (net (code "93") (name "Net-(PGB-D-PadC)") (class "Default")
      (node (ref "PGB-D") (pin "C") (pinfunction "C_C") (pintype "passive"))
      (node (ref "R26") (pin "2") (pinfunction "2_2") (pintype "passive"))
    )
    (net (code "94") (name "Net-(PGS-C-PadC)") (class "Default")
      (node (ref "PGS-C") (pin "C") (pinfunction "C_C") (pintype "passive"))
      (node (ref "R17") (pin "2") (pinfunction "2_2") (pintype "passive"))
    )
    (net (code "95") (name "Net-(PGS-D-PadC)") (class "Default")
      (node (ref "PGS-D") (pin "C") (pinfunction "C_C") (pintype "passive"))
      (node (ref "R24") (pin "2") (pinfunction "2_2") (pintype "passive"))
    )
    (net (code "96") (name "Net-(PWR-PadC)") (class "Default")
      (node (ref "PWR") (pin "C") (pinfunction "C_C") (pintype "passive"))
      (node (ref "R82") (pin "2") (pinfunction "2_2") (pintype "passive"))
    )
    (net (code "97") (name "Net-(R4-Pad2)") (class "Default")
      (node (ref "R4") (pin "2") (pinfunction "2_2") (pintype "passive"))
      (node (ref "U$37") (pin "5") (pinfunction "D1_5") (pintype "passive"))
      (node (ref "U$37") (pin "6") (pinfunction "D1_6") (pintype "passive"))
    )
    (net (code "98") (name "Net-(R5-Pad2)") (class "Default")
      (node (ref "R5") (pin "2") (pinfunction "2_2") (pintype "passive"))
      (node (ref "U$37") (pin "7") (pinfunction "D2_7") (pintype "passive"))
      (node (ref "U$37") (pin "8") (pinfunction "D2_8") (pintype "passive"))
    )
    (net (code "99") (name "Net-(R7-Pad1)") (class "Default")
      (node (ref "R7") (pin "1") (pinfunction "1_1") (pintype "passive"))
      (node (ref "U$36") (pin "5") (pinfunction "D1_5") (pintype "passive"))
      (node (ref "U$36") (pin "6") (pinfunction "D1_6") (pintype "passive"))
    )
    (net (code "100") (name "Net-(R28-Pad1)") (class "Default")
      (node (ref "R28") (pin "1") (pinfunction "1_1") (pintype "passive"))
      (node (ref "U$36") (pin "7") (pinfunction "D2_7") (pintype "passive"))
      (node (ref "U$36") (pin "8") (pinfunction "D2_8") (pintype "passive"))
    )
    (net (code "101") (name "Net-(TCXO-OUTPUT)") (class "Default")
      (node (ref "C1") (pin "2") (pinfunction "2_2") (pintype "passive"))
      (node (ref "TCXO") (pin "P$3") (pinfunction "OUTPUT_P$3") (pintype "bidirectional"))
    )
    (net (code "102") (name "Net-(U$1-1)") (class "Default")
      (node (ref "U$1") (pin "P$1") (pinfunction "1_P$1") (pintype "passive"))
      (node (ref "U$6") (pin "5") (pinfunction "D2_5") (pintype "passive"))
      (node (ref "U$6") (pin "6") (pinfunction "D2_6") (pintype "passive"))
    )
    (net (code "103") (name "Net-(U$2-BST)") (class "Default")
      (node (ref "C5.C") (pin "2") (pinfunction "2_2") (pintype "passive"))
      (node (ref "U$2") (pin "25") (pinfunction "BST_25") (pintype "bidirectional"))
    )
    (net (code "104") (name "Net-(U$2-CST)") (class "Default")
      (node (ref "C6.C") (pin "1") (pinfunction "1_1") (pintype "passive"))
      (node (ref "U$2") (pin "1") (pinfunction "CST_1") (pintype "bidirectional"))
    )
    (net (code "105") (name "Net-(U$2-DET)") (class "Default")
      (node (ref "R1.C") (pin "2") (pinfunction "2_2") (pintype "passive"))
      (node (ref "R2.C") (pin "1") (pinfunction "1_1") (pintype "passive"))
      (node (ref "U$2") (pin "10") (pinfunction "DET_10") (pintype "bidirectional"))
    )
    (net (code "106") (name "Net-(U$2-DVDT)") (class "Default")
      (node (ref "C8.C") (pin "1") (pinfunction "1_1") (pintype "passive"))
      (node (ref "U$2") (pin "7") (pinfunction "DVDT_7") (pintype "bidirectional"))
    )
    (net (code "107") (name "Net-(U$2-EN)") (class "Default")
      (node (ref "R11.C") (pin "1") (pinfunction "1_1") (pintype "passive"))
      (node (ref "R12.C") (pin "2") (pinfunction "2_2") (pintype "passive"))
      (node (ref "U$2") (pin "13") (pinfunction "EN_13") (pintype "bidirectional"))
    )
    (net (code "108") (name "Net-(U$2-FBS)") (class "Default")
      (node (ref "R5.C") (pin "2") (pinfunction "2_2") (pintype "passive"))
      (node (ref "R6.C") (pin "1") (pinfunction "1_1") (pintype "passive"))
      (node (ref "U$2") (pin "23") (pinfunction "FBS_23") (pintype "bidirectional"))
    )
    (net (code "109") (name "Net-(U$2-ICH)") (class "Default")
      (node (ref "R18.C") (pin "1") (pinfunction "1_1") (pintype "passive"))
      (node (ref "U$2") (pin "21") (pinfunction "ICH_21") (pintype "bidirectional"))
    )
    (net (code "110") (name "Net-(U$2-ILIM)") (class "Default")
      (node (ref "R7.C") (pin "2") (pinfunction "2_2") (pintype "passive"))
      (node (ref "U$2") (pin "8") (pinfunction "ILIM_8") (pintype "bidirectional"))
    )
    (net (code "111") (name "Net-(U$2-OVP)") (class "Default")
      (node (ref "R10.C") (pin "1") (pinfunction "1_1") (pintype "passive"))
      (node (ref "R9.C") (pin "2") (pinfunction "2_2") (pintype "passive"))
      (node (ref "U$2") (pin "4") (pinfunction "OVP_4") (pintype "bidirectional"))
    )
    (net (code "112") (name "Net-(U$2-RTEST)") (class "Default")
      (node (ref "R8.C") (pin "2") (pinfunction "2_2") (pintype "passive"))
      (node (ref "U$2") (pin "24") (pinfunction "RTEST_24") (pintype "bidirectional"))
    )
    (net (code "113") (name "Net-(U$2-SAS)") (class "Default")
      (node (ref "R13.C") (pin "2") (pinfunction "2_2") (pintype "passive"))
      (node (ref "U$2") (pin "5") (pinfunction "SAS_5") (pintype "bidirectional"))
    )
    (net (code "114") (name "Net-(U$2-SCL)") (class "Default")
      (node (ref "R17.C") (pin "1") (pinfunction "1_1") (pintype "passive"))
      (node (ref "U$2") (pin "19") (pinfunction "SCL_19") (pintype "bidirectional"))
    )
    (net (code "115") (name "Net-(U$2-SDA)") (class "Default")
      (node (ref "R16.C") (pin "1") (pinfunction "1_1") (pintype "passive"))
      (node (ref "U$2") (pin "18") (pinfunction "SDA_18") (pintype "bidirectional"))
    )
    (net (code "116") (name "Net-(U$2-TEMP)") (class "Default")
      (node (ref "R19.C") (pin "1") (pinfunction "1_1") (pintype "passive"))
      (node (ref "U$2") (pin "20") (pinfunction "TEMP_20") (pintype "bidirectional"))
    )
    (net (code "117") (name "Net-(U$2-TPOR)") (class "Default")
      (node (ref "C7.C") (pin "1") (pinfunction "1_1") (pintype "passive"))
      (node (ref "U$2") (pin "3") (pinfunction "TPOR_3") (pintype "bidirectional"))
    )
    (net (code "118") (name "Net-(U$5-BST)") (class "Default")
      (node (ref "C5.D") (pin "2") (pinfunction "2_2") (pintype "passive"))
      (node (ref "U$5") (pin "25") (pinfunction "BST_25") (pintype "bidirectional"))
    )
    (net (code "119") (name "Net-(U$5-CST)") (class "Default")
      (node (ref "C6.D") (pin "1") (pinfunction "1_1") (pintype "passive"))
      (node (ref "U$5") (pin "1") (pinfunction "CST_1") (pintype "bidirectional"))
    )
    (net (code "120") (name "Net-(U$5-DET)") (class "Default")
      (node (ref "R1.D") (pin "2") (pinfunction "2_2") (pintype "passive"))
      (node (ref "R2.D") (pin "1") (pinfunction "1_1") (pintype "passive"))
      (node (ref "U$5") (pin "10") (pinfunction "DET_10") (pintype "bidirectional"))
    )
    (net (code "121") (name "Net-(U$5-DVDT)") (class "Default")
      (node (ref "C8.D") (pin "1") (pinfunction "1_1") (pintype "passive"))
      (node (ref "U$5") (pin "7") (pinfunction "DVDT_7") (pintype "bidirectional"))
    )
    (net (code "122") (name "Net-(U$5-EN)") (class "Default")
      (node (ref "R11.D") (pin "1") (pinfunction "1_1") (pintype "passive"))
      (node (ref "R12.D") (pin "2") (pinfunction "2_2") (pintype "passive"))
      (node (ref "U$5") (pin "13") (pinfunction "EN_13") (pintype "bidirectional"))
    )
    (net (code "123") (name "Net-(U$5-FBS)") (class "Default")
      (node (ref "R5.D") (pin "2") (pinfunction "2_2") (pintype "passive"))
      (node (ref "R6.D") (pin "1") (pinfunction "1_1") (pintype "passive"))
      (node (ref "U$5") (pin "23") (pinfunction "FBS_23") (pintype "bidirectional"))
    )
    (net (code "124") (name "Net-(U$5-ICH)") (class "Default")
      (node (ref "R18.D") (pin "1") (pinfunction "1_1") (pintype "passive"))
      (node (ref "U$5") (pin "21") (pinfunction "ICH_21") (pintype "bidirectional"))
    )
    (net (code "125") (name "Net-(U$5-ILIM)") (class "Default")
      (node (ref "R7.D") (pin "2") (pinfunction "2_2") (pintype "passive"))
      (node (ref "U$5") (pin "8") (pinfunction "ILIM_8") (pintype "bidirectional"))
    )
    (net (code "126") (name "Net-(U$5-OVP)") (class "Default")
      (node (ref "R10.D") (pin "1") (pinfunction "1_1") (pintype "passive"))
      (node (ref "R9.D") (pin "2") (pinfunction "2_2") (pintype "passive"))
      (node (ref "U$5") (pin "4") (pinfunction "OVP_4") (pintype "bidirectional"))
    )
    (net (code "127") (name "Net-(U$5-RTEST)") (class "Default")
      (node (ref "R8.D") (pin "2") (pinfunction "2_2") (pintype "passive"))
      (node (ref "U$5") (pin "24") (pinfunction "RTEST_24") (pintype "bidirectional"))
    )
    (net (code "128") (name "Net-(U$5-SAS)") (class "Default")
      (node (ref "R13.D") (pin "2") (pinfunction "2_2") (pintype "passive"))
      (node (ref "U$5") (pin "5") (pinfunction "SAS_5") (pintype "bidirectional"))
    )
    (net (code "129") (name "Net-(U$5-SCL)") (class "Default")
      (node (ref "R17.D") (pin "1") (pinfunction "1_1") (pintype "passive"))
      (node (ref "U$5") (pin "19") (pinfunction "SCL_19") (pintype "bidirectional"))
    )
    (net (code "130") (name "Net-(U$5-SDA)") (class "Default")
      (node (ref "R16.D") (pin "1") (pinfunction "1_1") (pintype "passive"))
      (node (ref "U$5") (pin "18") (pinfunction "SDA_18") (pintype "bidirectional"))
    )
    (net (code "131") (name "Net-(U$5-TEMP)") (class "Default")
      (node (ref "R19.D") (pin "1") (pinfunction "1_1") (pintype "passive"))
      (node (ref "U$5") (pin "20") (pinfunction "TEMP_20") (pintype "bidirectional"))
    )
    (net (code "132") (name "Net-(U$5-TPOR)") (class "Default")
      (node (ref "C7.D") (pin "1") (pinfunction "1_1") (pintype "passive"))
      (node (ref "U$5") (pin "3") (pinfunction "TPOR_3") (pintype "bidirectional"))
    )
    (net (code "133") (name "Net-(U$6-G1)") (class "Default")
      (node (ref "R28") (pin "2") (pinfunction "2_2") (pintype "passive"))
      (node (ref "R31") (pin "2") (pinfunction "2_2") (pintype "passive"))
      (node (ref "U$6") (pin "2") (pinfunction "G1_2") (pintype "passive"))
    )
    (net (code "134") (name "Net-(U$6-G2)") (class "Default")
      (node (ref "R29") (pin "2") (pinfunction "2_2") (pintype "passive"))
      (node (ref "R7") (pin "2") (pinfunction "2_2") (pintype "passive"))
      (node (ref "U$6") (pin "4") (pinfunction "G2_4") (pintype "passive"))
    )
    (net (code "135") (name "Net-(U$9-1)") (class "Default")
      (node (ref "R22") (pin "2") (pinfunction "2_2") (pintype "passive"))
      (node (ref "U$13") (pin "2") (pinfunction "2_2") (pintype "passive"))
      (node (ref "U$9") (pin "P$1") (pinfunction "1_P$1") (pintype "passive"))
    )
    (net (code "136") (name "Net-(U$11-1)") (class "Default")
      (node (ref "R19") (pin "1") (pinfunction "1_1") (pintype "passive"))
      (node (ref "U$11") (pin "P$1") (pinfunction "1_P$1") (pintype "passive"))
      (node (ref "U$14") (pin "2") (pinfunction "2_2") (pintype "passive"))
    )
    (net (code "137") (name "Net-(U$17-1)") (class "Default")
      (node (ref "R21") (pin "1") (pinfunction "1_1") (pintype "passive"))
      (node (ref "U$16") (pin "2") (pinfunction "2_2") (pintype "passive"))
      (node (ref "U$17") (pin "P$1") (pinfunction "1_P$1") (pintype "passive"))
    )
    (net (code "138") (name "Net-(U$18-1)") (class "Default")
      (node (ref "R20") (pin "2") (pinfunction "2_2") (pintype "passive"))
      (node (ref "U$15") (pin "1") (pinfunction "1_1") (pintype "passive"))
      (node (ref "U$18") (pin "P$1") (pinfunction "1_P$1") (pintype "passive"))
    )
    (net (code "139") (name "Net-(U$22-1)") (class "Default")
      (node (ref "R14") (pin "1") (pinfunction "1_1") (pintype "passive"))
      (node (ref "U$20") (pin "1") (pinfunction "1_1") (pintype "passive"))
      (node (ref "U$22") (pin "P$1") (pinfunction "1_P$1") (pintype "passive"))
    )
    (net (code "140") (name "Net-(U$23-1)") (class "Default")
      (node (ref "R31") (pin "1") (pinfunction "1_1") (pintype "passive"))
      (node (ref "U$23") (pin "P$1") (pinfunction "1_P$1") (pintype "passive"))
      (node (ref "U$6") (pin "1") (pinfunction "S1_1") (pintype "passive"))
    )
    (net (code "141") (name "Net-(U$24-1)") (class "Default")
      (node (ref "R13") (pin "2") (pinfunction "2_2") (pintype "passive"))
      (node (ref "U$21") (pin "2") (pinfunction "2_2") (pintype "passive"))
      (node (ref "U$24") (pin "P$1") (pinfunction "1_P$1") (pintype "passive"))
    )
    (net (code "142") (name "Net-(U$27-1)") (class "Default")
      (node (ref "R9") (pin "1") (pinfunction "1_1") (pintype "passive"))
      (node (ref "U$26") (pin "2") (pinfunction "2_2") (pintype "passive"))
      (node (ref "U$27") (pin "P$1") (pinfunction "1_P$1") (pintype "passive"))
    )
    (net (code "143") (name "Net-(U$30-1)") (class "Default")
      (node (ref "R10") (pin "2") (pinfunction "2_2") (pintype "passive"))
      (node (ref "U$29") (pin "2") (pinfunction "2_2") (pintype "passive"))
      (node (ref "U$30") (pin "P$1") (pinfunction "1_P$1") (pintype "passive"))
    )
    (net (code "144") (name "Net-(U$34-G1)") (class "Default")
      (node (ref "R35") (pin "2") (pinfunction "2_2") (pintype "passive"))
      (node (ref "R5") (pin "1") (pinfunction "1_1") (pintype "passive"))
      (node (ref "U$34") (pin "2") (pinfunction "G1_2") (pintype "passive"))
    )
    (net (code "145") (name "Net-(U$34-G2)") (class "Default")
      (node (ref "R34") (pin "2") (pinfunction "2_2") (pintype "passive"))
      (node (ref "R4") (pin "1") (pinfunction "1_1") (pintype "passive"))
      (node (ref "U$34") (pin "4") (pinfunction "G2_4") (pintype "passive"))
    )
    (net (code "146") (name "Net-(U$34-S1)") (class "Default")
      (node (ref "R35") (pin "1") (pinfunction "1_1") (pintype "passive"))
      (node (ref "U$34") (pin "1") (pinfunction "S1_1") (pintype "passive"))
      (node (ref "U$55") (pin "P$1") (pinfunction "1_P$1") (pintype "passive"))
    )
    (net (code "147") (name "Net-(U$35-D1-Pad7)") (class "Default")
      (node (ref "U$35") (pin "5") (pinfunction "D2_5") (pintype "passive"))
      (node (ref "U$35") (pin "6") (pinfunction "D2_6") (pintype "passive"))
      (node (ref "U$35") (pin "7") (pinfunction "D1_7") (pintype "passive"))
      (node (ref "U$35") (pin "8") (pinfunction "D1_8") (pintype "passive"))
    )
    (net (code "148") (name "Net-(U$35-G1)") (class "Default")
      (node (ref "R40") (pin "2") (pinfunction "2_2") (pintype "passive"))
      (node (ref "R41") (pin "2") (pinfunction "2_2") (pintype "passive"))
      (node (ref "U$35") (pin "2") (pinfunction "G1_2") (pintype "passive"))
      (node (ref "U$35") (pin "4") (pinfunction "G2_4") (pintype "passive"))
      (node (ref "U$38") (pin "3") (pinfunction "D_3") (pintype "bidirectional"))
    )
    (net (code "149") (name "Net-(U$36-G1)") (class "Default")
      (node (ref "R1") (pin "2") (pinfunction "2_2") (pintype "passive"))
      (node (ref "R3") (pin "2") (pinfunction "2_2") (pintype "passive"))
      (node (ref "U$36") (pin "2") (pinfunction "G2_2") (pintype "passive"))
      (node (ref "U$36") (pin "4") (pinfunction "G1_4") (pintype "passive"))
    )
    (net (code "150") (name "Net-(U$37-G1)") (class "Default")
      (node (ref "R38") (pin "1") (pinfunction "1_1") (pintype "passive"))
      (node (ref "R39") (pin "1") (pinfunction "1_1") (pintype "passive"))
      (node (ref "U$37") (pin "2") (pinfunction "G2_2") (pintype "passive"))
      (node (ref "U$37") (pin "4") (pinfunction "G1_4") (pintype "passive"))
    )
    (net (code "151") (name "Net-(U$41-1)") (class "Default")
      (node (ref "R44") (pin "1") (pinfunction "1_1") (pintype "passive"))
      (node (ref "U$40") (pin "2") (pinfunction "2_2") (pintype "passive"))
      (node (ref "U$41") (pin "P$1") (pinfunction "1_P$1") (pintype "passive"))
    )
    (net (code "152") (name "Net-(U$42-1)") (class "Default")
      (node (ref "R43") (pin "2") (pinfunction "2_2") (pintype "passive"))
      (node (ref "U$39") (pin "1") (pinfunction "1_1") (pintype "passive"))
      (node (ref "U$42") (pin "P$1") (pinfunction "1_P$1") (pintype "passive"))
    )
    (net (code "153") (name "Net-(U$46-1)") (class "Default")
      (node (ref "R46") (pin "1") (pinfunction "1_1") (pintype "passive"))
      (node (ref "U$45") (pin "2") (pinfunction "2_2") (pintype "passive"))
      (node (ref "U$46") (pin "P$1") (pinfunction "1_P$1") (pintype "passive"))
    )
    (net (code "154") (name "Net-(U$47-1)") (class "Default")
      (node (ref "R45") (pin "2") (pinfunction "2_2") (pintype "passive"))
      (node (ref "U$44") (pin "1") (pinfunction "1_1") (pintype "passive"))
      (node (ref "U$47") (pin "P$1") (pinfunction "1_P$1") (pintype "passive"))
    )
    (net (code "155") (name "Net-(U$50-1)") (class "Default")
      (node (ref "R47") (pin "1") (pinfunction "1_1") (pintype "passive"))
      (node (ref "U$49") (pin "2") (pinfunction "2_2") (pintype "passive"))
      (node (ref "U$50") (pin "P$1") (pinfunction "1_P$1") (pintype "passive"))
    )
    (net (code "156") (name "Net-(U$53-1)") (class "Default")
      (node (ref "R48") (pin "2") (pinfunction "2_2") (pintype "passive"))
      (node (ref "U$52") (pin "2") (pinfunction "2_2") (pintype "passive"))
      (node (ref "U$53") (pin "P$1") (pinfunction "1_P$1") (pintype "passive"))
    )
    (net (code "157") (name "Net-(U$54-1)") (class "Default")
      (node (ref "U$34") (pin "5") (pinfunction "D2_5") (pintype "passive"))
      (node (ref "U$34") (pin "6") (pinfunction "D2_6") (pintype "passive"))
      (node (ref "U$54") (pin "P$1") (pinfunction "1_P$1") (pintype "passive"))
    )
    (net (code "158") (name "unconnected-(IC2-OSC_OUT-Pad6)") (class "Default")
      (node (ref "IC2") (pin "6") (pinfunction "OSC_OUT_6") (pintype "bidirectional"))
    )
    (net (code "159") (name "unconnected-(IC2-PA11-Pad32)") (class "Default")
      (node (ref "IC2") (pin "32") (pinfunction "PA11_32") (pintype "bidirectional"))
    )
    (net (code "160") (name "unconnected-(IC2-PA12-Pad33)") (class "Default")
      (node (ref "IC2") (pin "33") (pinfunction "PA12_33") (pintype "bidirectional"))
    )
    (net (code "161") (name "unconnected-(IC2-PB3-Pad39)") (class "Default")
      (node (ref "IC2") (pin "39") (pinfunction "PB3_39") (pintype "bidirectional"))
    )
    (net (code "162") (name "unconnected-(INVERT1-NC-PadP$1)") (class "Default")
      (node (ref "INVERT1") (pin "P$1") (pinfunction "NC_P$1") (pintype "bidirectional"))
    )
    (net (code "163") (name "unconnected-(JP1-Pad9)") (class "Default")
      (node (ref "JP1") (pin "9") (pinfunction "9_9") (pintype "passive"))
    )
    (net (code "164") (name "unconnected-(JP1-Pad10)") (class "Default")
      (node (ref "JP1") (pin "10") (pinfunction "10_10") (pintype "passive"))
    )
    (net (code "165") (name "unconnected-(U$12-12-PadP$12)") (class "Default")
      (node (ref "U$12") (pin "P$12") (pinfunction "12_P$12") (pintype "passive"))
    )
    (net (code "166") (name "unconnected-(U$12-13-PadP$13)") (class "Default")
      (node (ref "U$12") (pin "P$13") (pinfunction "13_P$13") (pintype "passive"))
    )
    (net (code "167") (name "unconnected-(U$12-14-PadP$14)") (class "Default")
      (node (ref "U$12") (pin "P$14") (pinfunction "14_P$14") (pintype "passive"))
    )
    (net (code "168") (name "unconnected-(U$12-15-PadP$15)") (class "Default")
      (node (ref "U$12") (pin "P$15") (pinfunction "15_P$15") (pintype "passive"))
    )
  )
)
